# Choin_tran1_0.net
KiCad netlist of a schematic drawn in Altium Designer
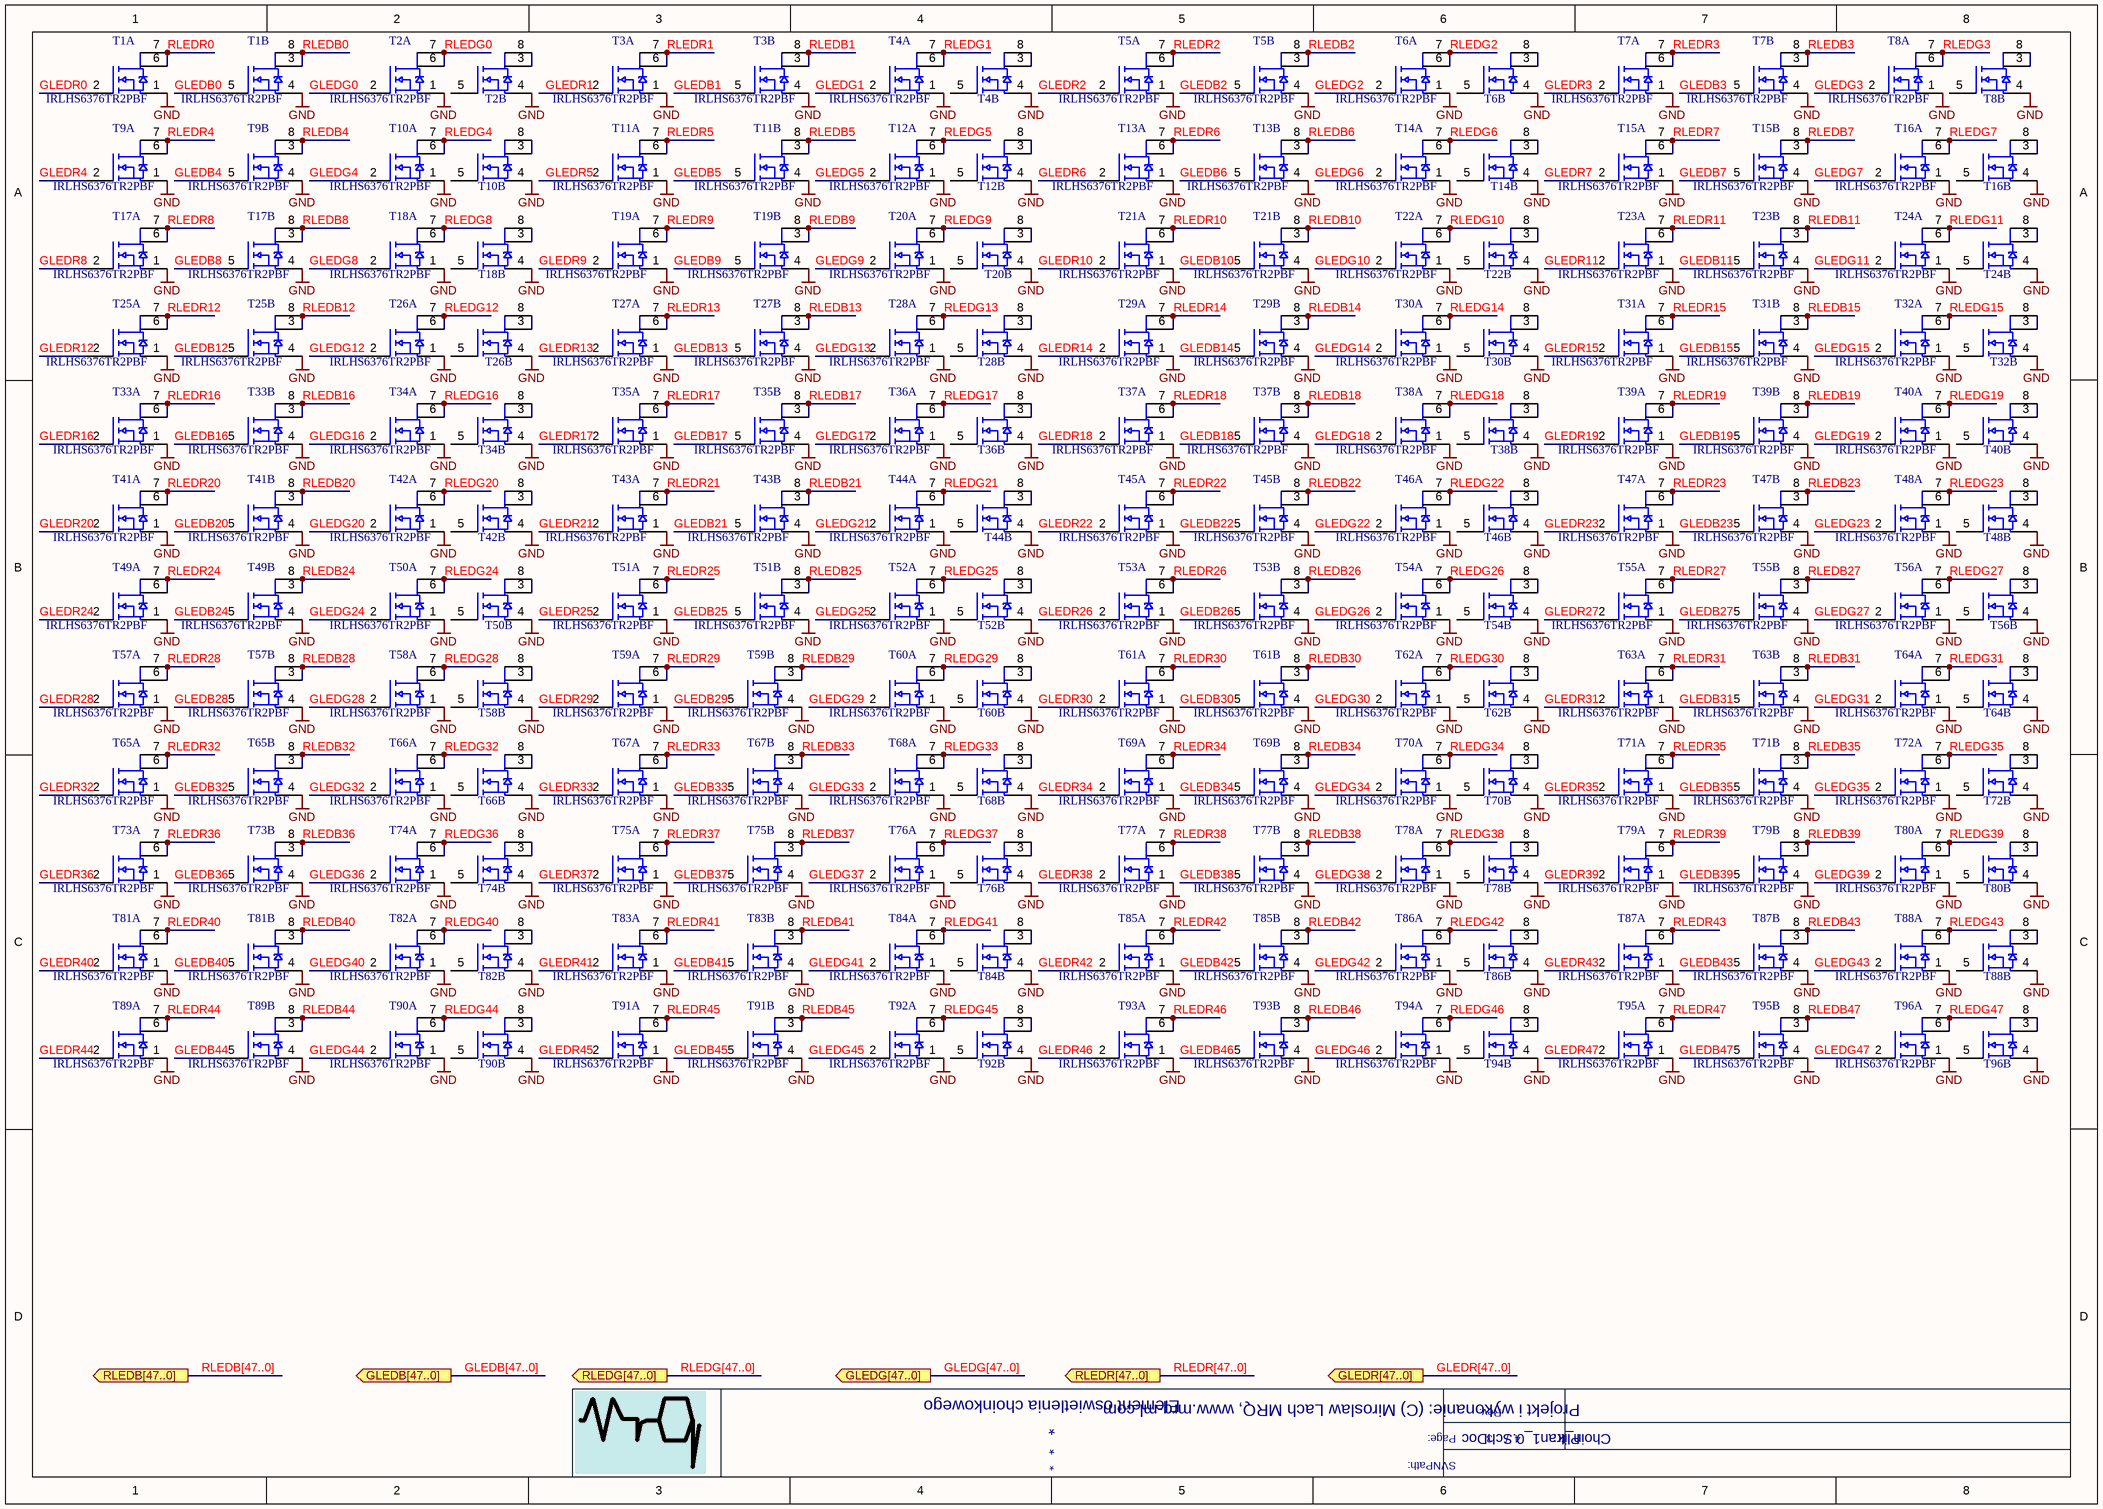
[diagram p0: Choin_tran1_0.SchDoc]

(export (version "E")
  (design (tool "Eeschema 10.0.6"))
  (components
    (comp (ref "T1")
      (value "IRLHS6376TR2PBF")
      (footprint "PQFN2X2DUAL")
      (libsource (lib "Parts") (part "IRLHS6376TR2PBF"))
    )
    (comp (ref "T2")
      (value "IRLHS6376TR2PBF")
      (footprint "PQFN2X2DUAL")
      (libsource (lib "Parts") (part "IRLHS6376TR2PBF"))
    )
    (comp (ref "T3")
      (value "IRLHS6376TR2PBF")
      (footprint "PQFN2X2DUAL")
      (libsource (lib "Parts") (part "IRLHS6376TR2PBF"))
    )
    (comp (ref "T4")
      (value "IRLHS6376TR2PBF")
      (footprint "PQFN2X2DUAL")
      (libsource (lib "Parts") (part "IRLHS6376TR2PBF"))
    )
    (comp (ref "T5")
      (value "IRLHS6376TR2PBF")
      (footprint "PQFN2X2DUAL")
      (libsource (lib "Parts") (part "IRLHS6376TR2PBF"))
    )
    (comp (ref "T6")
      (value "IRLHS6376TR2PBF")
      (footprint "PQFN2X2DUAL")
      (libsource (lib "Parts") (part "IRLHS6376TR2PBF"))
    )
    (comp (ref "T7")
      (value "IRLHS6376TR2PBF")
      (footprint "PQFN2X2DUAL")
      (libsource (lib "Parts") (part "IRLHS6376TR2PBF"))
    )
    (comp (ref "T8")
      (value "IRLHS6376TR2PBF")
      (footprint "PQFN2X2DUAL")
      (libsource (lib "Parts") (part "IRLHS6376TR2PBF"))
    )
    (comp (ref "T9")
      (value "IRLHS6376TR2PBF")
      (footprint "PQFN2X2DUAL")
      (libsource (lib "Parts") (part "IRLHS6376TR2PBF"))
    )
    (comp (ref "T10")
      (value "IRLHS6376TR2PBF")
      (footprint "PQFN2X2DUAL")
      (libsource (lib "Parts") (part "IRLHS6376TR2PBF"))
    )
    (comp (ref "T11")
      (value "IRLHS6376TR2PBF")
      (footprint "PQFN2X2DUAL")
      (libsource (lib "Parts") (part "IRLHS6376TR2PBF"))
    )
    (comp (ref "T12")
      (value "IRLHS6376TR2PBF")
      (footprint "PQFN2X2DUAL")
      (libsource (lib "Parts") (part "IRLHS6376TR2PBF"))
    )
    (comp (ref "T13")
      (value "IRLHS6376TR2PBF")
      (footprint "PQFN2X2DUAL")
      (libsource (lib "Parts") (part "IRLHS6376TR2PBF"))
    )
    (comp (ref "T14")
      (value "IRLHS6376TR2PBF")
      (footprint "PQFN2X2DUAL")
      (libsource (lib "Parts") (part "IRLHS6376TR2PBF"))
    )
    (comp (ref "T15")
      (value "IRLHS6376TR2PBF")
      (footprint "PQFN2X2DUAL")
      (libsource (lib "Parts") (part "IRLHS6376TR2PBF"))
    )
    (comp (ref "T16")
      (value "IRLHS6376TR2PBF")
      (footprint "PQFN2X2DUAL")
      (libsource (lib "Parts") (part "IRLHS6376TR2PBF"))
    )
    (comp (ref "T17")
      (value "IRLHS6376TR2PBF")
      (footprint "PQFN2X2DUAL")
      (libsource (lib "Parts") (part "IRLHS6376TR2PBF"))
    )
    (comp (ref "T18")
      (value "IRLHS6376TR2PBF")
      (footprint "PQFN2X2DUAL")
      (libsource (lib "Parts") (part "IRLHS6376TR2PBF"))
    )
    (comp (ref "T19")
      (value "IRLHS6376TR2PBF")
      (footprint "PQFN2X2DUAL")
      (libsource (lib "Parts") (part "IRLHS6376TR2PBF"))
    )
    (comp (ref "T20")
      (value "IRLHS6376TR2PBF")
      (footprint "PQFN2X2DUAL")
      (libsource (lib "Parts") (part "IRLHS6376TR2PBF"))
    )
    (comp (ref "T21")
      (value "IRLHS6376TR2PBF")
      (footprint "PQFN2X2DUAL")
      (libsource (lib "Parts") (part "IRLHS6376TR2PBF"))
    )
    (comp (ref "T22")
      (value "IRLHS6376TR2PBF")
      (footprint "PQFN2X2DUAL")
      (libsource (lib "Parts") (part "IRLHS6376TR2PBF"))
    )
    (comp (ref "T23")
      (value "IRLHS6376TR2PBF")
      (footprint "PQFN2X2DUAL")
      (libsource (lib "Parts") (part "IRLHS6376TR2PBF"))
    )
    (comp (ref "T24")
      (value "IRLHS6376TR2PBF")
      (footprint "PQFN2X2DUAL")
      (libsource (lib "Parts") (part "IRLHS6376TR2PBF"))
    )
    (comp (ref "T25")
      (value "IRLHS6376TR2PBF")
      (footprint "PQFN2X2DUAL")
      (libsource (lib "Parts") (part "IRLHS6376TR2PBF"))
    )
    (comp (ref "T26")
      (value "IRLHS6376TR2PBF")
      (footprint "PQFN2X2DUAL")
      (libsource (lib "Parts") (part "IRLHS6376TR2PBF"))
    )
    (comp (ref "T27")
      (value "IRLHS6376TR2PBF")
      (footprint "PQFN2X2DUAL")
      (libsource (lib "Parts") (part "IRLHS6376TR2PBF"))
    )
    (comp (ref "T28")
      (value "IRLHS6376TR2PBF")
      (footprint "PQFN2X2DUAL")
      (libsource (lib "Parts") (part "IRLHS6376TR2PBF"))
    )
    (comp (ref "T29")
      (value "IRLHS6376TR2PBF")
      (footprint "PQFN2X2DUAL")
      (libsource (lib "Parts") (part "IRLHS6376TR2PBF"))
    )
    (comp (ref "T30")
      (value "IRLHS6376TR2PBF")
      (footprint "PQFN2X2DUAL")
      (libsource (lib "Parts") (part "IRLHS6376TR2PBF"))
    )
    (comp (ref "T31")
      (value "IRLHS6376TR2PBF")
      (footprint "PQFN2X2DUAL")
      (libsource (lib "Parts") (part "IRLHS6376TR2PBF"))
    )
    (comp (ref "T32")
      (value "IRLHS6376TR2PBF")
      (footprint "PQFN2X2DUAL")
      (libsource (lib "Parts") (part "IRLHS6376TR2PBF"))
    )
    (comp (ref "T33")
      (value "IRLHS6376TR2PBF")
      (footprint "PQFN2X2DUAL")
      (libsource (lib "Parts") (part "IRLHS6376TR2PBF"))
    )
    (comp (ref "T34")
      (value "IRLHS6376TR2PBF")
      (footprint "PQFN2X2DUAL")
      (libsource (lib "Parts") (part "IRLHS6376TR2PBF"))
    )
    (comp (ref "T35")
      (value "IRLHS6376TR2PBF")
      (footprint "PQFN2X2DUAL")
      (libsource (lib "Parts") (part "IRLHS6376TR2PBF"))
    )
    (comp (ref "T36")
      (value "IRLHS6376TR2PBF")
      (footprint "PQFN2X2DUAL")
      (libsource (lib "Parts") (part "IRLHS6376TR2PBF"))
    )
    (comp (ref "T37")
      (value "IRLHS6376TR2PBF")
      (footprint "PQFN2X2DUAL")
      (libsource (lib "Parts") (part "IRLHS6376TR2PBF"))
    )
    (comp (ref "T38")
      (value "IRLHS6376TR2PBF")
      (footprint "PQFN2X2DUAL")
      (libsource (lib "Parts") (part "IRLHS6376TR2PBF"))
    )
    (comp (ref "T39")
      (value "IRLHS6376TR2PBF")
      (footprint "PQFN2X2DUAL")
      (libsource (lib "Parts") (part "IRLHS6376TR2PBF"))
    )
    (comp (ref "T40")
      (value "IRLHS6376TR2PBF")
      (footprint "PQFN2X2DUAL")
      (libsource (lib "Parts") (part "IRLHS6376TR2PBF"))
    )
    (comp (ref "T41")
      (value "IRLHS6376TR2PBF")
      (footprint "PQFN2X2DUAL")
      (libsource (lib "Parts") (part "IRLHS6376TR2PBF"))
    )
    (comp (ref "T42")
      (value "IRLHS6376TR2PBF")
      (footprint "PQFN2X2DUAL")
      (libsource (lib "Parts") (part "IRLHS6376TR2PBF"))
    )
    (comp (ref "T43")
      (value "IRLHS6376TR2PBF")
      (footprint "PQFN2X2DUAL")
      (libsource (lib "Parts") (part "IRLHS6376TR2PBF"))
    )
    (comp (ref "T44")
      (value "IRLHS6376TR2PBF")
      (footprint "PQFN2X2DUAL")
      (libsource (lib "Parts") (part "IRLHS6376TR2PBF"))
    )
    (comp (ref "T45")
      (value "IRLHS6376TR2PBF")
      (footprint "PQFN2X2DUAL")
      (libsource (lib "Parts") (part "IRLHS6376TR2PBF"))
    )
    (comp (ref "T46")
      (value "IRLHS6376TR2PBF")
      (footprint "PQFN2X2DUAL")
      (libsource (lib "Parts") (part "IRLHS6376TR2PBF"))
    )
    (comp (ref "T47")
      (value "IRLHS6376TR2PBF")
      (footprint "PQFN2X2DUAL")
      (libsource (lib "Parts") (part "IRLHS6376TR2PBF"))
    )
    (comp (ref "T48")
      (value "IRLHS6376TR2PBF")
      (footprint "PQFN2X2DUAL")
      (libsource (lib "Parts") (part "IRLHS6376TR2PBF"))
    )
    (comp (ref "T49")
      (value "IRLHS6376TR2PBF")
      (footprint "PQFN2X2DUAL")
      (libsource (lib "Parts") (part "IRLHS6376TR2PBF"))
    )
    (comp (ref "T50")
      (value "IRLHS6376TR2PBF")
      (footprint "PQFN2X2DUAL")
      (libsource (lib "Parts") (part "IRLHS6376TR2PBF"))
    )
    (comp (ref "T51")
      (value "IRLHS6376TR2PBF")
      (footprint "PQFN2X2DUAL")
      (libsource (lib "Parts") (part "IRLHS6376TR2PBF"))
    )
    (comp (ref "T52")
      (value "IRLHS6376TR2PBF")
      (footprint "PQFN2X2DUAL")
      (libsource (lib "Parts") (part "IRLHS6376TR2PBF"))
    )
    (comp (ref "T53")
      (value "IRLHS6376TR2PBF")
      (footprint "PQFN2X2DUAL")
      (libsource (lib "Parts") (part "IRLHS6376TR2PBF"))
    )
    (comp (ref "T54")
      (value "IRLHS6376TR2PBF")
      (footprint "PQFN2X2DUAL")
      (libsource (lib "Parts") (part "IRLHS6376TR2PBF"))
    )
    (comp (ref "T55")
      (value "IRLHS6376TR2PBF")
      (footprint "PQFN2X2DUAL")
      (libsource (lib "Parts") (part "IRLHS6376TR2PBF"))
    )
    (comp (ref "T56")
      (value "IRLHS6376TR2PBF")
      (footprint "PQFN2X2DUAL")
      (libsource (lib "Parts") (part "IRLHS6376TR2PBF"))
    )
    (comp (ref "T57")
      (value "IRLHS6376TR2PBF")
      (footprint "PQFN2X2DUAL")
      (libsource (lib "Parts") (part "IRLHS6376TR2PBF"))
    )
    (comp (ref "T58")
      (value "IRLHS6376TR2PBF")
      (footprint "PQFN2X2DUAL")
      (libsource (lib "Parts") (part "IRLHS6376TR2PBF"))
    )
    (comp (ref "T59")
      (value "IRLHS6376TR2PBF")
      (footprint "PQFN2X2DUAL")
      (libsource (lib "Parts") (part "IRLHS6376TR2PBF"))
    )
    (comp (ref "T60")
      (value "IRLHS6376TR2PBF")
      (footprint "PQFN2X2DUAL")
      (libsource (lib "Parts") (part "IRLHS6376TR2PBF"))
    )
    (comp (ref "T61")
      (value "IRLHS6376TR2PBF")
      (footprint "PQFN2X2DUAL")
      (libsource (lib "Parts") (part "IRLHS6376TR2PBF"))
    )
    (comp (ref "T62")
      (value "IRLHS6376TR2PBF")
      (footprint "PQFN2X2DUAL")
      (libsource (lib "Parts") (part "IRLHS6376TR2PBF"))
    )
    (comp (ref "T63")
      (value "IRLHS6376TR2PBF")
      (footprint "PQFN2X2DUAL")
      (libsource (lib "Parts") (part "IRLHS6376TR2PBF"))
    )
    (comp (ref "T64")
      (value "IRLHS6376TR2PBF")
      (footprint "PQFN2X2DUAL")
      (libsource (lib "Parts") (part "IRLHS6376TR2PBF"))
    )
    (comp (ref "T65")
      (value "IRLHS6376TR2PBF")
      (footprint "PQFN2X2DUAL")
      (libsource (lib "Parts") (part "IRLHS6376TR2PBF"))
    )
    (comp (ref "T66")
      (value "IRLHS6376TR2PBF")
      (footprint "PQFN2X2DUAL")
      (libsource (lib "Parts") (part "IRLHS6376TR2PBF"))
    )
    (comp (ref "T67")
      (value "IRLHS6376TR2PBF")
      (footprint "PQFN2X2DUAL")
      (libsource (lib "Parts") (part "IRLHS6376TR2PBF"))
    )
    (comp (ref "T68")
      (value "IRLHS6376TR2PBF")
      (footprint "PQFN2X2DUAL")
      (libsource (lib "Parts") (part "IRLHS6376TR2PBF"))
    )
    (comp (ref "T69")
      (value "IRLHS6376TR2PBF")
      (footprint "PQFN2X2DUAL")
      (libsource (lib "Parts") (part "IRLHS6376TR2PBF"))
    )
    (comp (ref "T70")
      (value "IRLHS6376TR2PBF")
      (footprint "PQFN2X2DUAL")
      (libsource (lib "Parts") (part "IRLHS6376TR2PBF"))
    )
    (comp (ref "T71")
      (value "IRLHS6376TR2PBF")
      (footprint "PQFN2X2DUAL")
      (libsource (lib "Parts") (part "IRLHS6376TR2PBF"))
    )
    (comp (ref "T72")
      (value "IRLHS6376TR2PBF")
      (footprint "PQFN2X2DUAL")
      (libsource (lib "Parts") (part "IRLHS6376TR2PBF"))
    )
    (comp (ref "T73")
      (value "IRLHS6376TR2PBF")
      (footprint "PQFN2X2DUAL")
      (libsource (lib "Parts") (part "IRLHS6376TR2PBF"))
    )
    (comp (ref "T74")
      (value "IRLHS6376TR2PBF")
      (footprint "PQFN2X2DUAL")
      (libsource (lib "Parts") (part "IRLHS6376TR2PBF"))
    )
    (comp (ref "T75")
      (value "IRLHS6376TR2PBF")
      (footprint "PQFN2X2DUAL")
      (libsource (lib "Parts") (part "IRLHS6376TR2PBF"))
    )
    (comp (ref "T76")
      (value "IRLHS6376TR2PBF")
      (footprint "PQFN2X2DUAL")
      (libsource (lib "Parts") (part "IRLHS6376TR2PBF"))
    )
    (comp (ref "T77")
      (value "IRLHS6376TR2PBF")
      (footprint "PQFN2X2DUAL")
      (libsource (lib "Parts") (part "IRLHS6376TR2PBF"))
    )
    (comp (ref "T78")
      (value "IRLHS6376TR2PBF")
      (footprint "PQFN2X2DUAL")
      (libsource (lib "Parts") (part "IRLHS6376TR2PBF"))
    )
    (comp (ref "T79")
      (value "IRLHS6376TR2PBF")
      (footprint "PQFN2X2DUAL")
      (libsource (lib "Parts") (part "IRLHS6376TR2PBF"))
    )
    (comp (ref "T80")
      (value "IRLHS6376TR2PBF")
      (footprint "PQFN2X2DUAL")
      (libsource (lib "Parts") (part "IRLHS6376TR2PBF"))
    )
    (comp (ref "T81")
      (value "IRLHS6376TR2PBF")
      (footprint "PQFN2X2DUAL")
      (libsource (lib "Parts") (part "IRLHS6376TR2PBF"))
    )
    (comp (ref "T82")
      (value "IRLHS6376TR2PBF")
      (footprint "PQFN2X2DUAL")
      (libsource (lib "Parts") (part "IRLHS6376TR2PBF"))
    )
    (comp (ref "T83")
      (value "IRLHS6376TR2PBF")
      (footprint "PQFN2X2DUAL")
      (libsource (lib "Parts") (part "IRLHS6376TR2PBF"))
    )
    (comp (ref "T84")
      (value "IRLHS6376TR2PBF")
      (footprint "PQFN2X2DUAL")
      (libsource (lib "Parts") (part "IRLHS6376TR2PBF"))
    )
    (comp (ref "T85")
      (value "IRLHS6376TR2PBF")
      (footprint "PQFN2X2DUAL")
      (libsource (lib "Parts") (part "IRLHS6376TR2PBF"))
    )
    (comp (ref "T86")
      (value "IRLHS6376TR2PBF")
      (footprint "PQFN2X2DUAL")
      (libsource (lib "Parts") (part "IRLHS6376TR2PBF"))
    )
    (comp (ref "T87")
      (value "IRLHS6376TR2PBF")
      (footprint "PQFN2X2DUAL")
      (libsource (lib "Parts") (part "IRLHS6376TR2PBF"))
    )
    (comp (ref "T88")
      (value "IRLHS6376TR2PBF")
      (footprint "PQFN2X2DUAL")
      (libsource (lib "Parts") (part "IRLHS6376TR2PBF"))
    )
    (comp (ref "T89")
      (value "IRLHS6376TR2PBF")
      (footprint "PQFN2X2DUAL")
      (libsource (lib "Parts") (part "IRLHS6376TR2PBF"))
    )
    (comp (ref "T90")
      (value "IRLHS6376TR2PBF")
      (footprint "PQFN2X2DUAL")
      (libsource (lib "Parts") (part "IRLHS6376TR2PBF"))
    )
    (comp (ref "T91")
      (value "IRLHS6376TR2PBF")
      (footprint "PQFN2X2DUAL")
      (libsource (lib "Parts") (part "IRLHS6376TR2PBF"))
    )
    (comp (ref "T92")
      (value "IRLHS6376TR2PBF")
      (footprint "PQFN2X2DUAL")
      (libsource (lib "Parts") (part "IRLHS6376TR2PBF"))
    )
    (comp (ref "T93")
      (value "IRLHS6376TR2PBF")
      (footprint "PQFN2X2DUAL")
      (libsource (lib "Parts") (part "IRLHS6376TR2PBF"))
    )
    (comp (ref "T94")
      (value "IRLHS6376TR2PBF")
      (footprint "PQFN2X2DUAL")
      (libsource (lib "Parts") (part "IRLHS6376TR2PBF"))
    )
    (comp (ref "T95")
      (value "IRLHS6376TR2PBF")
      (footprint "PQFN2X2DUAL")
      (libsource (lib "Parts") (part "IRLHS6376TR2PBF"))
    )
    (comp (ref "T96")
      (value "IRLHS6376TR2PBF")
      (footprint "PQFN2X2DUAL")
      (libsource (lib "Parts") (part "IRLHS6376TR2PBF"))
    )
  )
  (nets
    (net (code "1") (name "/GLEDB0") (class "Default")
      (node (ref "T1") (pin "5") (pinfunction "G2_5") (pintype "passive"))
    )
    (net (code "2") (name "/GLEDB1") (class "Default")
      (node (ref "T3") (pin "5") (pinfunction "G2_5") (pintype "passive"))
    )
    (net (code "3") (name "/GLEDB2") (class "Default")
      (node (ref "T5") (pin "5") (pinfunction "G2_5") (pintype "passive"))
    )
    (net (code "4") (name "/GLEDB3") (class "Default")
      (node (ref "T7") (pin "5") (pinfunction "G2_5") (pintype "passive"))
    )
    (net (code "5") (name "/GLEDB4") (class "Default")
      (node (ref "T9") (pin "5") (pinfunction "G2_5") (pintype "passive"))
    )
    (net (code "6") (name "/GLEDB5") (class "Default")
      (node (ref "T11") (pin "5") (pinfunction "G2_5") (pintype "passive"))
    )
    (net (code "7") (name "/GLEDB6") (class "Default")
      (node (ref "T13") (pin "5") (pinfunction "G2_5") (pintype "passive"))
    )
    (net (code "8") (name "/GLEDB7") (class "Default")
      (node (ref "T15") (pin "5") (pinfunction "G2_5") (pintype "passive"))
    )
    (net (code "9") (name "/GLEDB8") (class "Default")
      (node (ref "T17") (pin "5") (pinfunction "G2_5") (pintype "passive"))
    )
    (net (code "10") (name "/GLEDB9") (class "Default")
      (node (ref "T19") (pin "5") (pinfunction "G2_5") (pintype "passive"))
    )
    (net (code "11") (name "/GLEDB10") (class "Default")
      (node (ref "T21") (pin "5") (pinfunction "G2_5") (pintype "passive"))
    )
    (net (code "12") (name "/GLEDB11") (class "Default")
      (node (ref "T23") (pin "5") (pinfunction "G2_5") (pintype "passive"))
    )
    (net (code "13") (name "/GLEDB12") (class "Default")
      (node (ref "T25") (pin "5") (pinfunction "G2_5") (pintype "passive"))
    )
    (net (code "14") (name "/GLEDB13") (class "Default")
      (node (ref "T27") (pin "5") (pinfunction "G2_5") (pintype "passive"))
    )
    (net (code "15") (name "/GLEDB14") (class "Default")
      (node (ref "T29") (pin "5") (pinfunction "G2_5") (pintype "passive"))
    )
    (net (code "16") (name "/GLEDB15") (class "Default")
      (node (ref "T31") (pin "5") (pinfunction "G2_5") (pintype "passive"))
    )
    (net (code "17") (name "/GLEDB16") (class "Default")
      (node (ref "T33") (pin "5") (pinfunction "G2_5") (pintype "passive"))
    )
    (net (code "18") (name "/GLEDB17") (class "Default")
      (node (ref "T35") (pin "5") (pinfunction "G2_5") (pintype "passive"))
    )
    (net (code "19") (name "/GLEDB18") (class "Default")
      (node (ref "T37") (pin "5") (pinfunction "G2_5") (pintype "passive"))
    )
    (net (code "20") (name "/GLEDB19") (class "Default")
      (node (ref "T39") (pin "5") (pinfunction "G2_5") (pintype "passive"))
    )
    (net (code "21") (name "/GLEDB20") (class "Default")
      (node (ref "T41") (pin "5") (pinfunction "G2_5") (pintype "passive"))
    )
    (net (code "22") (name "/GLEDB21") (class "Default")
      (node (ref "T43") (pin "5") (pinfunction "G2_5") (pintype "passive"))
    )
    (net (code "23") (name "/GLEDB22") (class "Default")
      (node (ref "T45") (pin "5") (pinfunction "G2_5") (pintype "passive"))
    )
    (net (code "24") (name "/GLEDB23") (class "Default")
      (node (ref "T47") (pin "5") (pinfunction "G2_5") (pintype "passive"))
    )
    (net (code "25") (name "/GLEDB24") (class "Default")
      (node (ref "T49") (pin "5") (pinfunction "G2_5") (pintype "passive"))
    )
    (net (code "26") (name "/GLEDB25") (class "Default")
      (node (ref "T51") (pin "5") (pinfunction "G2_5") (pintype "passive"))
    )
    (net (code "27") (name "/GLEDB26") (class "Default")
      (node (ref "T53") (pin "5") (pinfunction "G2_5") (pintype "passive"))
    )
    (net (code "28") (name "/GLEDB27") (class "Default")
      (node (ref "T55") (pin "5") (pinfunction "G2_5") (pintype "passive"))
    )
    (net (code "29") (name "/GLEDB28") (class "Default")
      (node (ref "T57") (pin "5") (pinfunction "G2_5") (pintype "passive"))
    )
    (net (code "30") (name "/GLEDB29") (class "Default")
      (node (ref "T59") (pin "5") (pinfunction "G2_5") (pintype "passive"))
    )
    (net (code "31") (name "/GLEDB30") (class "Default")
      (node (ref "T61") (pin "5") (pinfunction "G2_5") (pintype "passive"))
    )
    (net (code "32") (name "/GLEDB31") (class "Default")
      (node (ref "T63") (pin "5") (pinfunction "G2_5") (pintype "passive"))
    )
    (net (code "33") (name "/GLEDB32") (class "Default")
      (node (ref "T65") (pin "5") (pinfunction "G2_5") (pintype "passive"))
    )
    (net (code "34") (name "/GLEDB33") (class "Default")
      (node (ref "T67") (pin "5") (pinfunction "G2_5") (pintype "passive"))
    )
    (net (code "35") (name "/GLEDB34") (class "Default")
      (node (ref "T69") (pin "5") (pinfunction "G2_5") (pintype "passive"))
    )
    (net (code "36") (name "/GLEDB35") (class "Default")
      (node (ref "T71") (pin "5") (pinfunction "G2_5") (pintype "passive"))
    )
    (net (code "37") (name "/GLEDB36") (class "Default")
      (node (ref "T73") (pin "5") (pinfunction "G2_5") (pintype "passive"))
    )
    (net (code "38") (name "/GLEDB37") (class "Default")
      (node (ref "T75") (pin "5") (pinfunction "G2_5") (pintype "passive"))
    )
    (net (code "39") (name "/GLEDB38") (class "Default")
      (node (ref "T77") (pin "5") (pinfunction "G2_5") (pintype "passive"))
    )
    (net (code "40") (name "/GLEDB39") (class "Default")
      (node (ref "T79") (pin "5") (pinfunction "G2_5") (pintype "passive"))
    )
    (net (code "41") (name "/GLEDB40") (class "Default")
      (node (ref "T81") (pin "5") (pinfunction "G2_5") (pintype "passive"))
    )
    (net (code "42") (name "/GLEDB41") (class "Default")
      (node (ref "T83") (pin "5") (pinfunction "G2_5") (pintype "passive"))
    )
    (net (code "43") (name "/GLEDB42") (class "Default")
      (node (ref "T85") (pin "5") (pinfunction "G2_5") (pintype "passive"))
    )
    (net (code "44") (name "/GLEDB43") (class "Default")
      (node (ref "T87") (pin "5") (pinfunction "G2_5") (pintype "passive"))
    )
    (net (code "45") (name "/GLEDB44") (class "Default")
      (node (ref "T89") (pin "5") (pinfunction "G2_5") (pintype "passive"))
    )
    (net (code "46") (name "/GLEDB45") (class "Default")
      (node (ref "T91") (pin "5") (pinfunction "G2_5") (pintype "passive"))
    )
    (net (code "47") (name "/GLEDB46") (class "Default")
      (node (ref "T93") (pin "5") (pinfunction "G2_5") (pintype "passive"))
    )
    (net (code "48") (name "/GLEDB47") (class "Default")
      (node (ref "T95") (pin "5") (pinfunction "G2_5") (pintype "passive"))
    )
    (net (code "50") (name "/GLEDG0") (class "Default")
      (node (ref "T2") (pin "2") (pinfunction "G1_2") (pintype "passive"))
    )
    (net (code "51") (name "/GLEDG1") (class "Default")
      (node (ref "T4") (pin "2") (pinfunction "G1_2") (pintype "passive"))
    )
    (net (code "52") (name "/GLEDG2") (class "Default")
      (node (ref "T6") (pin "2") (pinfunction "G1_2") (pintype "passive"))
    )
    (net (code "53") (name "/GLEDG3") (class "Default")
      (node (ref "T8") (pin "2") (pinfunction "G1_2") (pintype "passive"))
    )
    (net (code "54") (name "/GLEDG4") (class "Default")
      (node (ref "T10") (pin "2") (pinfunction "G1_2") (pintype "passive"))
    )
    (net (code "55") (name "/GLEDG5") (class "Default")
      (node (ref "T12") (pin "2") (pinfunction "G1_2") (pintype "passive"))
    )
    (net (code "56") (name "/GLEDG6") (class "Default")
      (node (ref "T14") (pin "2") (pinfunction "G1_2") (pintype "passive"))
    )
    (net (code "57") (name "/GLEDG7") (class "Default")
      (node (ref "T16") (pin "2") (pinfunction "G1_2") (pintype "passive"))
    )
    (net (code "58") (name "/GLEDG8") (class "Default")
      (node (ref "T18") (pin "2") (pinfunction "G1_2") (pintype "passive"))
    )
    (net (code "59") (name "/GLEDG9") (class "Default")
      (node (ref "T20") (pin "2") (pinfunction "G1_2") (pintype "passive"))
    )
    (net (code "60") (name "/GLEDG10") (class "Default")
      (node (ref "T22") (pin "2") (pinfunction "G1_2") (pintype "passive"))
    )
    (net (code "61") (name "/GLEDG11") (class "Default")
      (node (ref "T24") (pin "2") (pinfunction "G1_2") (pintype "passive"))
    )
    (net (code "62") (name "/GLEDG12") (class "Default")
      (node (ref "T26") (pin "2") (pinfunction "G1_2") (pintype "passive"))
    )
    (net (code "63") (name "/GLEDG13") (class "Default")
      (node (ref "T28") (pin "2") (pinfunction "G1_2") (pintype "passive"))
    )
    (net (code "64") (name "/GLEDG14") (class "Default")
      (node (ref "T30") (pin "2") (pinfunction "G1_2") (pintype "passive"))
    )
    (net (code "65") (name "/GLEDG15") (class "Default")
      (node (ref "T32") (pin "2") (pinfunction "G1_2") (pintype "passive"))
    )
    (net (code "66") (name "/GLEDG16") (class "Default")
      (node (ref "T34") (pin "2") (pinfunction "G1_2") (pintype "passive"))
    )
    (net (code "67") (name "/GLEDG17") (class "Default")
      (node (ref "T36") (pin "2") (pinfunction "G1_2") (pintype "passive"))
    )
    (net (code "68") (name "/GLEDG18") (class "Default")
      (node (ref "T38") (pin "2") (pinfunction "G1_2") (pintype "passive"))
    )
    (net (code "69") (name "/GLEDG19") (class "Default")
      (node (ref "T40") (pin "2") (pinfunction "G1_2") (pintype "passive"))
    )
    (net (code "70") (name "/GLEDG20") (class "Default")
      (node (ref "T42") (pin "2") (pinfunction "G1_2") (pintype "passive"))
    )
    (net (code "71") (name "/GLEDG21") (class "Default")
      (node (ref "T44") (pin "2") (pinfunction "G1_2") (pintype "passive"))
    )
    (net (code "72") (name "/GLEDG22") (class "Default")
      (node (ref "T46") (pin "2") (pinfunction "G1_2") (pintype "passive"))
    )
    (net (code "73") (name "/GLEDG23") (class "Default")
      (node (ref "T48") (pin "2") (pinfunction "G1_2") (pintype "passive"))
    )
    (net (code "74") (name "/GLEDG24") (class "Default")
      (node (ref "T50") (pin "2") (pinfunction "G1_2") (pintype "passive"))
    )
    (net (code "75") (name "/GLEDG25") (class "Default")
      (node (ref "T52") (pin "2") (pinfunction "G1_2") (pintype "passive"))
    )
    (net (code "76") (name "/GLEDG26") (class "Default")
      (node (ref "T54") (pin "2") (pinfunction "G1_2") (pintype "passive"))
    )
    (net (code "77") (name "/GLEDG27") (class "Default")
      (node (ref "T56") (pin "2") (pinfunction "G1_2") (pintype "passive"))
    )
    (net (code "78") (name "/GLEDG28") (class "Default")
      (node (ref "T58") (pin "2") (pinfunction "G1_2") (pintype "passive"))
    )
    (net (code "79") (name "/GLEDG29") (class "Default")
      (node (ref "T60") (pin "2") (pinfunction "G1_2") (pintype "passive"))
    )
    (net (code "80") (name "/GLEDG30") (class "Default")
      (node (ref "T62") (pin "2") (pinfunction "G1_2") (pintype "passive"))
    )
    (net (code "81") (name "/GLEDG31") (class "Default")
      (node (ref "T64") (pin "2") (pinfunction "G1_2") (pintype "passive"))
    )
    (net (code "82") (name "/GLEDG32") (class "Default")
      (node (ref "T66") (pin "2") (pinfunction "G1_2") (pintype "passive"))
    )
    (net (code "83") (name "/GLEDG33") (class "Default")
      (node (ref "T68") (pin "2") (pinfunction "G1_2") (pintype "passive"))
    )
    (net (code "84") (name "/GLEDG34") (class "Default")
      (node (ref "T70") (pin "2") (pinfunction "G1_2") (pintype "passive"))
    )
    (net (code "85") (name "/GLEDG35") (class "Default")
      (node (ref "T72") (pin "2") (pinfunction "G1_2") (pintype "passive"))
    )
    (net (code "86") (name "/GLEDG36") (class "Default")
      (node (ref "T74") (pin "2") (pinfunction "G1_2") (pintype "passive"))
    )
    (net (code "87") (name "/GLEDG37") (class "Default")
      (node (ref "T76") (pin "2") (pinfunction "G1_2") (pintype "passive"))
    )
    (net (code "88") (name "/GLEDG38") (class "Default")
      (node (ref "T78") (pin "2") (pinfunction "G1_2") (pintype "passive"))
    )
    (net (code "89") (name "/GLEDG39") (class "Default")
      (node (ref "T80") (pin "2") (pinfunction "G1_2") (pintype "passive"))
    )
    (net (code "90") (name "/GLEDG40") (class "Default")
      (node (ref "T82") (pin "2") (pinfunction "G1_2") (pintype "passive"))
    )
    (net (code "91") (name "/GLEDG41") (class "Default")
      (node (ref "T84") (pin "2") (pinfunction "G1_2") (pintype "passive"))
    )
    (net (code "92") (name "/GLEDG42") (class "Default")
      (node (ref "T86") (pin "2") (pinfunction "G1_2") (pintype "passive"))
    )
    (net (code "93") (name "/GLEDG43") (class "Default")
      (node (ref "T88") (pin "2") (pinfunction "G1_2") (pintype "passive"))
    )
    (net (code "94") (name "/GLEDG44") (class "Default")
      (node (ref "T90") (pin "2") (pinfunction "G1_2") (pintype "passive"))
    )
    (net (code "95") (name "/GLEDG45") (class "Default")
      (node (ref "T92") (pin "2") (pinfunction "G1_2") (pintype "passive"))
    )
    (net (code "96") (name "/GLEDG46") (class "Default")
      (node (ref "T94") (pin "2") (pinfunction "G1_2") (pintype "passive"))
    )
    (net (code "97") (name "/GLEDG47") (class "Default")
      (node (ref "T96") (pin "2") (pinfunction "G1_2") (pintype "passive"))
    )
    (net (code "99") (name "/GLEDR0") (class "Default")
      (node (ref "T1") (pin "2") (pinfunction "G1_2") (pintype "passive"))
    )
    (net (code "100") (name "/GLEDR1") (class "Default")
      (node (ref "T3") (pin "2") (pinfunction "G1_2") (pintype "passive"))
    )
    (net (code "101") (name "/GLEDR2") (class "Default")
      (node (ref "T5") (pin "2") (pinfunction "G1_2") (pintype "passive"))
    )
    (net (code "102") (name "/GLEDR3") (class "Default")
      (node (ref "T7") (pin "2") (pinfunction "G1_2") (pintype "passive"))
    )
    (net (code "103") (name "/GLEDR4") (class "Default")
      (node (ref "T9") (pin "2") (pinfunction "G1_2") (pintype "passive"))
    )
    (net (code "104") (name "/GLEDR5") (class "Default")
      (node (ref "T11") (pin "2") (pinfunction "G1_2") (pintype "passive"))
    )
    (net (code "105") (name "/GLEDR6") (class "Default")
      (node (ref "T13") (pin "2") (pinfunction "G1_2") (pintype "passive"))
    )
    (net (code "106") (name "/GLEDR7") (class "Default")
      (node (ref "T15") (pin "2") (pinfunction "G1_2") (pintype "passive"))
    )
    (net (code "107") (name "/GLEDR8") (class "Default")
      (node (ref "T17") (pin "2") (pinfunction "G1_2") (pintype "passive"))
    )
    (net (code "108") (name "/GLEDR9") (class "Default")
      (node (ref "T19") (pin "2") (pinfunction "G1_2") (pintype "passive"))
    )
    (net (code "109") (name "/GLEDR10") (class "Default")
      (node (ref "T21") (pin "2") (pinfunction "G1_2") (pintype "passive"))
    )
    (net (code "110") (name "/GLEDR11") (class "Default")
      (node (ref "T23") (pin "2") (pinfunction "G1_2") (pintype "passive"))
    )
    (net (code "111") (name "/GLEDR12") (class "Default")
      (node (ref "T25") (pin "2") (pinfunction "G1_2") (pintype "passive"))
    )
    (net (code "112") (name "/GLEDR13") (class "Default")
      (node (ref "T27") (pin "2") (pinfunction "G1_2") (pintype "passive"))
    )
    (net (code "113") (name "/GLEDR14") (class "Default")
      (node (ref "T29") (pin "2") (pinfunction "G1_2") (pintype "passive"))
    )
    (net (code "114") (name "/GLEDR15") (class "Default")
      (node (ref "T31") (pin "2") (pinfunction "G1_2") (pintype "passive"))
    )
    (net (code "115") (name "/GLEDR16") (class "Default")
      (node (ref "T33") (pin "2") (pinfunction "G1_2") (pintype "passive"))
    )
    (net (code "116") (name "/GLEDR17") (class "Default")
      (node (ref "T35") (pin "2") (pinfunction "G1_2") (pintype "passive"))
    )
    (net (code "117") (name "/GLEDR18") (class "Default")
      (node (ref "T37") (pin "2") (pinfunction "G1_2") (pintype "passive"))
    )
    (net (code "118") (name "/GLEDR19") (class "Default")
      (node (ref "T39") (pin "2") (pinfunction "G1_2") (pintype "passive"))
    )
    (net (code "119") (name "/GLEDR20") (class "Default")
      (node (ref "T41") (pin "2") (pinfunction "G1_2") (pintype "passive"))
    )
    (net (code "120") (name "/GLEDR21") (class "Default")
      (node (ref "T43") (pin "2") (pinfunction "G1_2") (pintype "passive"))
    )
    (net (code "121") (name "/GLEDR22") (class "Default")
      (node (ref "T45") (pin "2") (pinfunction "G1_2") (pintype "passive"))
    )
    (net (code "122") (name "/GLEDR23") (class "Default")
      (node (ref "T47") (pin "2") (pinfunction "G1_2") (pintype "passive"))
    )
    (net (code "123") (name "/GLEDR24") (class "Default")
      (node (ref "T49") (pin "2") (pinfunction "G1_2") (pintype "passive"))
    )
    (net (code "124") (name "/GLEDR25") (class "Default")
      (node (ref "T51") (pin "2") (pinfunction "G1_2") (pintype "passive"))
    )
    (net (code "125") (name "/GLEDR26") (class "Default")
      (node (ref "T53") (pin "2") (pinfunction "G1_2") (pintype "passive"))
    )
    (net (code "126") (name "/GLEDR27") (class "Default")
      (node (ref "T55") (pin "2") (pinfunction "G1_2") (pintype "passive"))
    )
    (net (code "127") (name "/GLEDR28") (class "Default")
      (node (ref "T57") (pin "2") (pinfunction "G1_2") (pintype "passive"))
    )
    (net (code "128") (name "/GLEDR29") (class "Default")
      (node (ref "T59") (pin "2") (pinfunction "G1_2") (pintype "passive"))
    )
    (net (code "129") (name "/GLEDR30") (class "Default")
      (node (ref "T61") (pin "2") (pinfunction "G1_2") (pintype "passive"))
    )
    (net (code "130") (name "/GLEDR31") (class "Default")
      (node (ref "T63") (pin "2") (pinfunction "G1_2") (pintype "passive"))
    )
    (net (code "131") (name "/GLEDR32") (class "Default")
      (node (ref "T65") (pin "2") (pinfunction "G1_2") (pintype "passive"))
    )
    (net (code "132") (name "/GLEDR33") (class "Default")
      (node (ref "T67") (pin "2") (pinfunction "G1_2") (pintype "passive"))
    )
    (net (code "133") (name "/GLEDR34") (class "Default")
      (node (ref "T69") (pin "2") (pinfunction "G1_2") (pintype "passive"))
    )
    (net (code "134") (name "/GLEDR35") (class "Default")
      (node (ref "T71") (pin "2") (pinfunction "G1_2") (pintype "passive"))
    )
    (net (code "135") (name "/GLEDR36") (class "Default")
      (node (ref "T73") (pin "2") (pinfunction "G1_2") (pintype "passive"))
    )
    (net (code "136") (name "/GLEDR37") (class "Default")
      (node (ref "T75") (pin "2") (pinfunction "G1_2") (pintype "passive"))
    )
    (net (code "137") (name "/GLEDR38") (class "Default")
      (node (ref "T77") (pin "2") (pinfunction "G1_2") (pintype "passive"))
    )
    (net (code "138") (name "/GLEDR39") (class "Default")
      (node (ref "T79") (pin "2") (pinfunction "G1_2") (pintype "passive"))
    )
    (net (code "139") (name "/GLEDR40") (class "Default")
      (node (ref "T81") (pin "2") (pinfunction "G1_2") (pintype "passive"))
    )
    (net (code "140") (name "/GLEDR41") (class "Default")
      (node (ref "T83") (pin "2") (pinfunction "G1_2") (pintype "passive"))
    )
    (net (code "141") (name "/GLEDR42") (class "Default")
      (node (ref "T85") (pin "2") (pinfunction "G1_2") (pintype "passive"))
    )
    (net (code "142") (name "/GLEDR43") (class "Default")
      (node (ref "T87") (pin "2") (pinfunction "G1_2") (pintype "passive"))
    )
    (net (code "143") (name "/GLEDR44") (class "Default")
      (node (ref "T89") (pin "2") (pinfunction "G1_2") (pintype "passive"))
    )
    (net (code "144") (name "/GLEDR45") (class "Default")
      (node (ref "T91") (pin "2") (pinfunction "G1_2") (pintype "passive"))
    )
    (net (code "145") (name "/GLEDR46") (class "Default")
      (node (ref "T93") (pin "2") (pinfunction "G1_2") (pintype "passive"))
    )
    (net (code "146") (name "/GLEDR47") (class "Default")
      (node (ref "T95") (pin "2") (pinfunction "G1_2") (pintype "passive"))
    )
    (net (code "148") (name "/RLEDB0") (class "Default")
      (node (ref "T1") (pin "3") (pinfunction "D2_3") (pintype "passive"))
      (node (ref "T1") (pin "8") (pinfunction "D2_8") (pintype "passive"))
    )
    (net (code "149") (name "/RLEDB1") (class "Default")
      (node (ref "T3") (pin "3") (pinfunction "D2_3") (pintype "passive"))
      (node (ref "T3") (pin "8") (pinfunction "D2_8") (pintype "passive"))
    )
    (net (code "150") (name "/RLEDB2") (class "Default")
      (node (ref "T5") (pin "3") (pinfunction "D2_3") (pintype "passive"))
      (node (ref "T5") (pin "8") (pinfunction "D2_8") (pintype "passive"))
    )
    (net (code "151") (name "/RLEDB3") (class "Default")
      (node (ref "T7") (pin "3") (pinfunction "D2_3") (pintype "passive"))
      (node (ref "T7") (pin "8") (pinfunction "D2_8") (pintype "passive"))
    )
    (net (code "152") (name "/RLEDB4") (class "Default")
      (node (ref "T9") (pin "3") (pinfunction "D2_3") (pintype "passive"))
      (node (ref "T9") (pin "8") (pinfunction "D2_8") (pintype "passive"))
    )
    (net (code "153") (name "/RLEDB5") (class "Default")
      (node (ref "T11") (pin "3") (pinfunction "D2_3") (pintype "passive"))
      (node (ref "T11") (pin "8") (pinfunction "D2_8") (pintype "passive"))
    )
    (net (code "154") (name "/RLEDB6") (class "Default")
      (node (ref "T13") (pin "3") (pinfunction "D2_3") (pintype "passive"))
      (node (ref "T13") (pin "8") (pinfunction "D2_8") (pintype "passive"))
    )
    (net (code "155") (name "/RLEDB7") (class "Default")
      (node (ref "T15") (pin "3") (pinfunction "D2_3") (pintype "passive"))
      (node (ref "T15") (pin "8") (pinfunction "D2_8") (pintype "passive"))
    )
    (net (code "156") (name "/RLEDB8") (class "Default")
      (node (ref "T17") (pin "3") (pinfunction "D2_3") (pintype "passive"))
      (node (ref "T17") (pin "8") (pinfunction "D2_8") (pintype "passive"))
    )
    (net (code "157") (name "/RLEDB9") (class "Default")
      (node (ref "T19") (pin "3") (pinfunction "D2_3") (pintype "passive"))
      (node (ref "T19") (pin "8") (pinfunction "D2_8") (pintype "passive"))
    )
    (net (code "158") (name "/RLEDB10") (class "Default")
      (node (ref "T21") (pin "3") (pinfunction "D2_3") (pintype "passive"))
      (node (ref "T21") (pin "8") (pinfunction "D2_8") (pintype "passive"))
    )
    (net (code "159") (name "/RLEDB11") (class "Default")
      (node (ref "T23") (pin "3") (pinfunction "D2_3") (pintype "passive"))
      (node (ref "T23") (pin "8") (pinfunction "D2_8") (pintype "passive"))
    )
    (net (code "160") (name "/RLEDB12") (class "Default")
      (node (ref "T25") (pin "3") (pinfunction "D2_3") (pintype "passive"))
      (node (ref "T25") (pin "8") (pinfunction "D2_8") (pintype "passive"))
    )
    (net (code "161") (name "/RLEDB13") (class "Default")
      (node (ref "T27") (pin "3") (pinfunction "D2_3") (pintype "passive"))
      (node (ref "T27") (pin "8") (pinfunction "D2_8") (pintype "passive"))
    )
    (net (code "162") (name "/RLEDB14") (class "Default")
      (node (ref "T29") (pin "3") (pinfunction "D2_3") (pintype "passive"))
      (node (ref "T29") (pin "8") (pinfunction "D2_8") (pintype "passive"))
    )
    (net (code "163") (name "/RLEDB15") (class "Default")
      (node (ref "T31") (pin "3") (pinfunction "D2_3") (pintype "passive"))
      (node (ref "T31") (pin "8") (pinfunction "D2_8") (pintype "passive"))
    )
    (net (code "164") (name "/RLEDB16") (class "Default")
      (node (ref "T33") (pin "3") (pinfunction "D2_3") (pintype "passive"))
      (node (ref "T33") (pin "8") (pinfunction "D2_8") (pintype "passive"))
    )
    (net (code "165") (name "/RLEDB17") (class "Default")
      (node (ref "T35") (pin "3") (pinfunction "D2_3") (pintype "passive"))
      (node (ref "T35") (pin "8") (pinfunction "D2_8") (pintype "passive"))
    )
    (net (code "166") (name "/RLEDB18") (class "Default")
      (node (ref "T37") (pin "3") (pinfunction "D2_3") (pintype "passive"))
      (node (ref "T37") (pin "8") (pinfunction "D2_8") (pintype "passive"))
    )
    (net (code "167") (name "/RLEDB19") (class "Default")
      (node (ref "T39") (pin "3") (pinfunction "D2_3") (pintype "passive"))
      (node (ref "T39") (pin "8") (pinfunction "D2_8") (pintype "passive"))
    )
    (net (code "168") (name "/RLEDB20") (class "Default")
      (node (ref "T41") (pin "3") (pinfunction "D2_3") (pintype "passive"))
      (node (ref "T41") (pin "8") (pinfunction "D2_8") (pintype "passive"))
    )
    (net (code "169") (name "/RLEDB21") (class "Default")
      (node (ref "T43") (pin "3") (pinfunction "D2_3") (pintype "passive"))
      (node (ref "T43") (pin "8") (pinfunction "D2_8") (pintype "passive"))
    )
    (net (code "170") (name "/RLEDB22") (class "Default")
      (node (ref "T45") (pin "3") (pinfunction "D2_3") (pintype "passive"))
      (node (ref "T45") (pin "8") (pinfunction "D2_8") (pintype "passive"))
    )
    (net (code "171") (name "/RLEDB23") (class "Default")
      (node (ref "T47") (pin "3") (pinfunction "D2_3") (pintype "passive"))
      (node (ref "T47") (pin "8") (pinfunction "D2_8") (pintype "passive"))
    )
    (net (code "172") (name "/RLEDB24") (class "Default")
      (node (ref "T49") (pin "3") (pinfunction "D2_3") (pintype "passive"))
      (node (ref "T49") (pin "8") (pinfunction "D2_8") (pintype "passive"))
    )
    (net (code "173") (name "/RLEDB25") (class "Default")
      (node (ref "T51") (pin "3") (pinfunction "D2_3") (pintype "passive"))
      (node (ref "T51") (pin "8") (pinfunction "D2_8") (pintype "passive"))
    )
    (net (code "174") (name "/RLEDB26") (class "Default")
      (node (ref "T53") (pin "3") (pinfunction "D2_3") (pintype "passive"))
      (node (ref "T53") (pin "8") (pinfunction "D2_8") (pintype "passive"))
    )
    (net (code "175") (name "/RLEDB27") (class "Default")
      (node (ref "T55") (pin "3") (pinfunction "D2_3") (pintype "passive"))
      (node (ref "T55") (pin "8") (pinfunction "D2_8") (pintype "passive"))
    )
    (net (code "176") (name "/RLEDB28") (class "Default")
      (node (ref "T57") (pin "3") (pinfunction "D2_3") (pintype "passive"))
      (node (ref "T57") (pin "8") (pinfunction "D2_8") (pintype "passive"))
    )
    (net (code "177") (name "/RLEDB29") (class "Default")
      (node (ref "T59") (pin "3") (pinfunction "D2_3") (pintype "passive"))
      (node (ref "T59") (pin "8") (pinfunction "D2_8") (pintype "passive"))
    )
    (net (code "178") (name "/RLEDB30") (class "Default")
      (node (ref "T61") (pin "3") (pinfunction "D2_3") (pintype "passive"))
      (node (ref "T61") (pin "8") (pinfunction "D2_8") (pintype "passive"))
    )
    (net (code "179") (name "/RLEDB31") (class "Default")
      (node (ref "T63") (pin "3") (pinfunction "D2_3") (pintype "passive"))
      (node (ref "T63") (pin "8") (pinfunction "D2_8") (pintype "passive"))
    )
    (net (code "180") (name "/RLEDB32") (class "Default")
      (node (ref "T65") (pin "3") (pinfunction "D2_3") (pintype "passive"))
      (node (ref "T65") (pin "8") (pinfunction "D2_8") (pintype "passive"))
    )
    (net (code "181") (name "/RLEDB33") (class "Default")
      (node (ref "T67") (pin "3") (pinfunction "D2_3") (pintype "passive"))
      (node (ref "T67") (pin "8") (pinfunction "D2_8") (pintype "passive"))
    )
    (net (code "182") (name "/RLEDB34") (class "Default")
      (node (ref "T69") (pin "3") (pinfunction "D2_3") (pintype "passive"))
      (node (ref "T69") (pin "8") (pinfunction "D2_8") (pintype "passive"))
    )
    (net (code "183") (name "/RLEDB35") (class "Default")
      (node (ref "T71") (pin "3") (pinfunction "D2_3") (pintype "passive"))
      (node (ref "T71") (pin "8") (pinfunction "D2_8") (pintype "passive"))
    )
    (net (code "184") (name "/RLEDB36") (class "Default")
      (node (ref "T73") (pin "3") (pinfunction "D2_3") (pintype "passive"))
      (node (ref "T73") (pin "8") (pinfunction "D2_8") (pintype "passive"))
    )
    (net (code "185") (name "/RLEDB37") (class "Default")
      (node (ref "T75") (pin "3") (pinfunction "D2_3") (pintype "passive"))
      (node (ref "T75") (pin "8") (pinfunction "D2_8") (pintype "passive"))
    )
    (net (code "186") (name "/RLEDB38") (class "Default")
      (node (ref "T77") (pin "3") (pinfunction "D2_3") (pintype "passive"))
      (node (ref "T77") (pin "8") (pinfunction "D2_8") (pintype "passive"))
    )
    (net (code "187") (name "/RLEDB39") (class "Default")
      (node (ref "T79") (pin "3") (pinfunction "D2_3") (pintype "passive"))
      (node (ref "T79") (pin "8") (pinfunction "D2_8") (pintype "passive"))
    )
    (net (code "188") (name "/RLEDB40") (class "Default")
      (node (ref "T81") (pin "3") (pinfunction "D2_3") (pintype "passive"))
      (node (ref "T81") (pin "8") (pinfunction "D2_8") (pintype "passive"))
    )
    (net (code "189") (name "/RLEDB41") (class "Default")
      (node (ref "T83") (pin "3") (pinfunction "D2_3") (pintype "passive"))
      (node (ref "T83") (pin "8") (pinfunction "D2_8") (pintype "passive"))
    )
    (net (code "190") (name "/RLEDB42") (class "Default")
      (node (ref "T85") (pin "3") (pinfunction "D2_3") (pintype "passive"))
      (node (ref "T85") (pin "8") (pinfunction "D2_8") (pintype "passive"))
    )
    (net (code "191") (name "/RLEDB43") (class "Default")
      (node (ref "T87") (pin "3") (pinfunction "D2_3") (pintype "passive"))
      (node (ref "T87") (pin "8") (pinfunction "D2_8") (pintype "passive"))
    )
    (net (code "192") (name "/RLEDB44") (class "Default")
      (node (ref "T89") (pin "3") (pinfunction "D2_3") (pintype "passive"))
      (node (ref "T89") (pin "8") (pinfunction "D2_8") (pintype "passive"))
    )
    (net (code "193") (name "/RLEDB45") (class "Default")
      (node (ref "T91") (pin "3") (pinfunction "D2_3") (pintype "passive"))
      (node (ref "T91") (pin "8") (pinfunction "D2_8") (pintype "passive"))
    )
    (net (code "194") (name "/RLEDB46") (class "Default")
      (node (ref "T93") (pin "3") (pinfunction "D2_3") (pintype "passive"))
      (node (ref "T93") (pin "8") (pinfunction "D2_8") (pintype "passive"))
    )
    (net (code "195") (name "/RLEDB47") (class "Default")
      (node (ref "T95") (pin "3") (pinfunction "D2_3") (pintype "passive"))
      (node (ref "T95") (pin "8") (pinfunction "D2_8") (pintype "passive"))
    )
    (net (code "197") (name "/RLEDG0") (class "Default")
      (node (ref "T2") (pin "6") (pinfunction "D1_6") (pintype "passive"))
      (node (ref "T2") (pin "7") (pinfunction "D1_7") (pintype "passive"))
    )
    (net (code "198") (name "/RLEDG1") (class "Default")
      (node (ref "T4") (pin "6") (pinfunction "D1_6") (pintype "passive"))
      (node (ref "T4") (pin "7") (pinfunction "D1_7") (pintype "passive"))
    )
    (net (code "199") (name "/RLEDG2") (class "Default")
      (node (ref "T6") (pin "6") (pinfunction "D1_6") (pintype "passive"))
      (node (ref "T6") (pin "7") (pinfunction "D1_7") (pintype "passive"))
    )
    (net (code "200") (name "/RLEDG3") (class "Default")
      (node (ref "T8") (pin "6") (pinfunction "D1_6") (pintype "passive"))
      (node (ref "T8") (pin "7") (pinfunction "D1_7") (pintype "passive"))
    )
    (net (code "201") (name "/RLEDG4") (class "Default")
      (node (ref "T10") (pin "6") (pinfunction "D1_6") (pintype "passive"))
      (node (ref "T10") (pin "7") (pinfunction "D1_7") (pintype "passive"))
    )
    (net (code "202") (name "/RLEDG5") (class "Default")
      (node (ref "T12") (pin "6") (pinfunction "D1_6") (pintype "passive"))
      (node (ref "T12") (pin "7") (pinfunction "D1_7") (pintype "passive"))
    )
    (net (code "203") (name "/RLEDG6") (class "Default")
      (node (ref "T14") (pin "6") (pinfunction "D1_6") (pintype "passive"))
      (node (ref "T14") (pin "7") (pinfunction "D1_7") (pintype "passive"))
    )
    (net (code "204") (name "/RLEDG7") (class "Default")
      (node (ref "T16") (pin "6") (pinfunction "D1_6") (pintype "passive"))
      (node (ref "T16") (pin "7") (pinfunction "D1_7") (pintype "passive"))
    )
    (net (code "205") (name "/RLEDG8") (class "Default")
      (node (ref "T18") (pin "6") (pinfunction "D1_6") (pintype "passive"))
      (node (ref "T18") (pin "7") (pinfunction "D1_7") (pintype "passive"))
    )
    (net (code "206") (name "/RLEDG9") (class "Default")
      (node (ref "T20") (pin "6") (pinfunction "D1_6") (pintype "passive"))
      (node (ref "T20") (pin "7") (pinfunction "D1_7") (pintype "passive"))
    )
    (net (code "207") (name "/RLEDG10") (class "Default")
      (node (ref "T22") (pin "6") (pinfunction "D1_6") (pintype "passive"))
      (node (ref "T22") (pin "7") (pinfunction "D1_7") (pintype "passive"))
    )
    (net (code "208") (name "/RLEDG11") (class "Default")
      (node (ref "T24") (pin "6") (pinfunction "D1_6") (pintype "passive"))
      (node (ref "T24") (pin "7") (pinfunction "D1_7") (pintype "passive"))
    )
    (net (code "209") (name "/RLEDG12") (class "Default")
      (node (ref "T26") (pin "6") (pinfunction "D1_6") (pintype "passive"))
      (node (ref "T26") (pin "7") (pinfunction "D1_7") (pintype "passive"))
    )
    (net (code "210") (name "/RLEDG13") (class "Default")
      (node (ref "T28") (pin "6") (pinfunction "D1_6") (pintype "passive"))
      (node (ref "T28") (pin "7") (pinfunction "D1_7") (pintype "passive"))
    )
    (net (code "211") (name "/RLEDG14") (class "Default")
      (node (ref "T30") (pin "6") (pinfunction "D1_6") (pintype "passive"))
      (node (ref "T30") (pin "7") (pinfunction "D1_7") (pintype "passive"))
    )
    (net (code "212") (name "/RLEDG15") (class "Default")
      (node (ref "T32") (pin "6") (pinfunction "D1_6") (pintype "passive"))
      (node (ref "T32") (pin "7") (pinfunction "D1_7") (pintype "passive"))
    )
    (net (code "213") (name "/RLEDG16") (class "Default")
      (node (ref "T34") (pin "6") (pinfunction "D1_6") (pintype "passive"))
      (node (ref "T34") (pin "7") (pinfunction "D1_7") (pintype "passive"))
    )
    (net (code "214") (name "/RLEDG17") (class "Default")
      (node (ref "T36") (pin "6") (pinfunction "D1_6") (pintype "passive"))
      (node (ref "T36") (pin "7") (pinfunction "D1_7") (pintype "passive"))
    )
    (net (code "215") (name "/RLEDG18") (class "Default")
      (node (ref "T38") (pin "6") (pinfunction "D1_6") (pintype "passive"))
      (node (ref "T38") (pin "7") (pinfunction "D1_7") (pintype "passive"))
    )
    (net (code "216") (name "/RLEDG19") (class "Default")
      (node (ref "T40") (pin "6") (pinfunction "D1_6") (pintype "passive"))
      (node (ref "T40") (pin "7") (pinfunction "D1_7") (pintype "passive"))
    )
    (net (code "217") (name "/RLEDG20") (class "Default")
      (node (ref "T42") (pin "6") (pinfunction "D1_6") (pintype "passive"))
      (node (ref "T42") (pin "7") (pinfunction "D1_7") (pintype "passive"))
    )
    (net (code "218") (name "/RLEDG21") (class "Default")
      (node (ref "T44") (pin "6") (pinfunction "D1_6") (pintype "passive"))
      (node (ref "T44") (pin "7") (pinfunction "D1_7") (pintype "passive"))
    )
    (net (code "219") (name "/RLEDG22") (class "Default")
      (node (ref "T46") (pin "6") (pinfunction "D1_6") (pintype "passive"))
      (node (ref "T46") (pin "7") (pinfunction "D1_7") (pintype "passive"))
    )
    (net (code "220") (name "/RLEDG23") (class "Default")
      (node (ref "T48") (pin "6") (pinfunction "D1_6") (pintype "passive"))
      (node (ref "T48") (pin "7") (pinfunction "D1_7") (pintype "passive"))
    )
    (net (code "221") (name "/RLEDG24") (class "Default")
      (node (ref "T50") (pin "6") (pinfunction "D1_6") (pintype "passive"))
      (node (ref "T50") (pin "7") (pinfunction "D1_7") (pintype "passive"))
    )
    (net (code "222") (name "/RLEDG25") (class "Default")
      (node (ref "T52") (pin "6") (pinfunction "D1_6") (pintype "passive"))
      (node (ref "T52") (pin "7") (pinfunction "D1_7") (pintype "passive"))
    )
    (net (code "223") (name "/RLEDG26") (class "Default")
      (node (ref "T54") (pin "6") (pinfunction "D1_6") (pintype "passive"))
      (node (ref "T54") (pin "7") (pinfunction "D1_7") (pintype "passive"))
    )
    (net (code "224") (name "/RLEDG27") (class "Default")
      (node (ref "T56") (pin "6") (pinfunction "D1_6") (pintype "passive"))
      (node (ref "T56") (pin "7") (pinfunction "D1_7") (pintype "passive"))
    )
    (net (code "225") (name "/RLEDG28") (class "Default")
      (node (ref "T58") (pin "6") (pinfunction "D1_6") (pintype "passive"))
      (node (ref "T58") (pin "7") (pinfunction "D1_7") (pintype "passive"))
    )
    (net (code "226") (name "/RLEDG29") (class "Default")
      (node (ref "T60") (pin "6") (pinfunction "D1_6") (pintype "passive"))
      (node (ref "T60") (pin "7") (pinfunction "D1_7") (pintype "passive"))
    )
    (net (code "227") (name "/RLEDG30") (class "Default")
      (node (ref "T62") (pin "6") (pinfunction "D1_6") (pintype "passive"))
      (node (ref "T62") (pin "7") (pinfunction "D1_7") (pintype "passive"))
    )
    (net (code "228") (name "/RLEDG31") (class "Default")
      (node (ref "T64") (pin "6") (pinfunction "D1_6") (pintype "passive"))
      (node (ref "T64") (pin "7") (pinfunction "D1_7") (pintype "passive"))
    )
    (net (code "229") (name "/RLEDG32") (class "Default")
      (node (ref "T66") (pin "6") (pinfunction "D1_6") (pintype "passive"))
      (node (ref "T66") (pin "7") (pinfunction "D1_7") (pintype "passive"))
    )
    (net (code "230") (name "/RLEDG33") (class "Default")
      (node (ref "T68") (pin "6") (pinfunction "D1_6") (pintype "passive"))
      (node (ref "T68") (pin "7") (pinfunction "D1_7") (pintype "passive"))
    )
    (net (code "231") (name "/RLEDG34") (class "Default")
      (node (ref "T70") (pin "6") (pinfunction "D1_6") (pintype "passive"))
      (node (ref "T70") (pin "7") (pinfunction "D1_7") (pintype "passive"))
    )
    (net (code "232") (name "/RLEDG35") (class "Default")
      (node (ref "T72") (pin "6") (pinfunction "D1_6") (pintype "passive"))
      (node (ref "T72") (pin "7") (pinfunction "D1_7") (pintype "passive"))
    )
    (net (code "233") (name "/RLEDG36") (class "Default")
      (node (ref "T74") (pin "6") (pinfunction "D1_6") (pintype "passive"))
      (node (ref "T74") (pin "7") (pinfunction "D1_7") (pintype "passive"))
    )
    (net (code "234") (name "/RLEDG37") (class "Default")
      (node (ref "T76") (pin "6") (pinfunction "D1_6") (pintype "passive"))
      (node (ref "T76") (pin "7") (pinfunction "D1_7") (pintype "passive"))
    )
    (net (code "235") (name "/RLEDG38") (class "Default")
      (node (ref "T78") (pin "6") (pinfunction "D1_6") (pintype "passive"))
      (node (ref "T78") (pin "7") (pinfunction "D1_7") (pintype "passive"))
    )
    (net (code "236") (name "/RLEDG39") (class "Default")
      (node (ref "T80") (pin "6") (pinfunction "D1_6") (pintype "passive"))
      (node (ref "T80") (pin "7") (pinfunction "D1_7") (pintype "passive"))
    )
    (net (code "237") (name "/RLEDG40") (class "Default")
      (node (ref "T82") (pin "6") (pinfunction "D1_6") (pintype "passive"))
      (node (ref "T82") (pin "7") (pinfunction "D1_7") (pintype "passive"))
    )
    (net (code "238") (name "/RLEDG41") (class "Default")
      (node (ref "T84") (pin "6") (pinfunction "D1_6") (pintype "passive"))
      (node (ref "T84") (pin "7") (pinfunction "D1_7") (pintype "passive"))
    )
    (net (code "239") (name "/RLEDG42") (class "Default")
      (node (ref "T86") (pin "6") (pinfunction "D1_6") (pintype "passive"))
      (node (ref "T86") (pin "7") (pinfunction "D1_7") (pintype "passive"))
    )
    (net (code "240") (name "/RLEDG43") (class "Default")
      (node (ref "T88") (pin "6") (pinfunction "D1_6") (pintype "passive"))
      (node (ref "T88") (pin "7") (pinfunction "D1_7") (pintype "passive"))
    )
    (net (code "241") (name "/RLEDG44") (class "Default")
      (node (ref "T90") (pin "6") (pinfunction "D1_6") (pintype "passive"))
      (node (ref "T90") (pin "7") (pinfunction "D1_7") (pintype "passive"))
    )
    (net (code "242") (name "/RLEDG45") (class "Default")
      (node (ref "T92") (pin "6") (pinfunction "D1_6") (pintype "passive"))
      (node (ref "T92") (pin "7") (pinfunction "D1_7") (pintype "passive"))
    )
    (net (code "243") (name "/RLEDG46") (class "Default")
      (node (ref "T94") (pin "6") (pinfunction "D1_6") (pintype "passive"))
      (node (ref "T94") (pin "7") (pinfunction "D1_7") (pintype "passive"))
    )
    (net (code "244") (name "/RLEDG47") (class "Default")
      (node (ref "T96") (pin "6") (pinfunction "D1_6") (pintype "passive"))
      (node (ref "T96") (pin "7") (pinfunction "D1_7") (pintype "passive"))
    )
    (net (code "246") (name "/RLEDR0") (class "Default")
      (node (ref "T1") (pin "6") (pinfunction "D1_6") (pintype "passive"))
      (node (ref "T1") (pin "7") (pinfunction "D1_7") (pintype "passive"))
    )
    (net (code "247") (name "/RLEDR1") (class "Default")
      (node (ref "T3") (pin "6") (pinfunction "D1_6") (pintype "passive"))
      (node (ref "T3") (pin "7") (pinfunction "D1_7") (pintype "passive"))
    )
    (net (code "248") (name "/RLEDR2") (class "Default")
      (node (ref "T5") (pin "6") (pinfunction "D1_6") (pintype "passive"))
      (node (ref "T5") (pin "7") (pinfunction "D1_7") (pintype "passive"))
    )
    (net (code "249") (name "/RLEDR3") (class "Default")
      (node (ref "T7") (pin "6") (pinfunction "D1_6") (pintype "passive"))
      (node (ref "T7") (pin "7") (pinfunction "D1_7") (pintype "passive"))
    )
    (net (code "250") (name "/RLEDR4") (class "Default")
      (node (ref "T9") (pin "6") (pinfunction "D1_6") (pintype "passive"))
      (node (ref "T9") (pin "7") (pinfunction "D1_7") (pintype "passive"))
    )
    (net (code "251") (name "/RLEDR5") (class "Default")
      (node (ref "T11") (pin "6") (pinfunction "D1_6") (pintype "passive"))
      (node (ref "T11") (pin "7") (pinfunction "D1_7") (pintype "passive"))
    )
    (net (code "252") (name "/RLEDR6") (class "Default")
      (node (ref "T13") (pin "6") (pinfunction "D1_6") (pintype "passive"))
      (node (ref "T13") (pin "7") (pinfunction "D1_7") (pintype "passive"))
    )
    (net (code "253") (name "/RLEDR7") (class "Default")
      (node (ref "T15") (pin "6") (pinfunction "D1_6") (pintype "passive"))
      (node (ref "T15") (pin "7") (pinfunction "D1_7") (pintype "passive"))
    )
    (net (code "254") (name "/RLEDR8") (class "Default")
      (node (ref "T17") (pin "6") (pinfunction "D1_6") (pintype "passive"))
      (node (ref "T17") (pin "7") (pinfunction "D1_7") (pintype "passive"))
    )
    (net (code "255") (name "/RLEDR9") (class "Default")
      (node (ref "T19") (pin "6") (pinfunction "D1_6") (pintype "passive"))
      (node (ref "T19") (pin "7") (pinfunction "D1_7") (pintype "passive"))
    )
    (net (code "256") (name "/RLEDR10") (class "Default")
      (node (ref "T21") (pin "6") (pinfunction "D1_6") (pintype "passive"))
      (node (ref "T21") (pin "7") (pinfunction "D1_7") (pintype "passive"))
    )
    (net (code "257") (name "/RLEDR11") (class "Default")
      (node (ref "T23") (pin "6") (pinfunction "D1_6") (pintype "passive"))
      (node (ref "T23") (pin "7") (pinfunction "D1_7") (pintype "passive"))
    )
    (net (code "258") (name "/RLEDR12") (class "Default")
      (node (ref "T25") (pin "6") (pinfunction "D1_6") (pintype "passive"))
      (node (ref "T25") (pin "7") (pinfunction "D1_7") (pintype "passive"))
    )
    (net (code "259") (name "/RLEDR13") (class "Default")
      (node (ref "T27") (pin "6") (pinfunction "D1_6") (pintype "passive"))
      (node (ref "T27") (pin "7") (pinfunction "D1_7") (pintype "passive"))
    )
    (net (code "260") (name "/RLEDR14") (class "Default")
      (node (ref "T29") (pin "6") (pinfunction "D1_6") (pintype "passive"))
      (node (ref "T29") (pin "7") (pinfunction "D1_7") (pintype "passive"))
    )
    (net (code "261") (name "/RLEDR15") (class "Default")
      (node (ref "T31") (pin "6") (pinfunction "D1_6") (pintype "passive"))
      (node (ref "T31") (pin "7") (pinfunction "D1_7") (pintype "passive"))
    )
    (net (code "262") (name "/RLEDR16") (class "Default")
      (node (ref "T33") (pin "6") (pinfunction "D1_6") (pintype "passive"))
      (node (ref "T33") (pin "7") (pinfunction "D1_7") (pintype "passive"))
    )
    (net (code "263") (name "/RLEDR17") (class "Default")
      (node (ref "T35") (pin "6") (pinfunction "D1_6") (pintype "passive"))
      (node (ref "T35") (pin "7") (pinfunction "D1_7") (pintype "passive"))
    )
    (net (code "264") (name "/RLEDR18") (class "Default")
      (node (ref "T37") (pin "6") (pinfunction "D1_6") (pintype "passive"))
      (node (ref "T37") (pin "7") (pinfunction "D1_7") (pintype "passive"))
    )
    (net (code "265") (name "/RLEDR19") (class "Default")
      (node (ref "T39") (pin "6") (pinfunction "D1_6") (pintype "passive"))
      (node (ref "T39") (pin "7") (pinfunction "D1_7") (pintype "passive"))
    )
    (net (code "266") (name "/RLEDR20") (class "Default")
      (node (ref "T41") (pin "6") (pinfunction "D1_6") (pintype "passive"))
      (node (ref "T41") (pin "7") (pinfunction "D1_7") (pintype "passive"))
    )
    (net (code "267") (name "/RLEDR21") (class "Default")
      (node (ref "T43") (pin "6") (pinfunction "D1_6") (pintype "passive"))
      (node (ref "T43") (pin "7") (pinfunction "D1_7") (pintype "passive"))
    )
    (net (code "268") (name "/RLEDR22") (class "Default")
      (node (ref "T45") (pin "6") (pinfunction "D1_6") (pintype "passive"))
      (node (ref "T45") (pin "7") (pinfunction "D1_7") (pintype "passive"))
    )
    (net (code "269") (name "/RLEDR23") (class "Default")
      (node (ref "T47") (pin "6") (pinfunction "D1_6") (pintype "passive"))
      (node (ref "T47") (pin "7") (pinfunction "D1_7") (pintype "passive"))
    )
    (net (code "270") (name "/RLEDR24") (class "Default")
      (node (ref "T49") (pin "6") (pinfunction "D1_6") (pintype "passive"))
      (node (ref "T49") (pin "7") (pinfunction "D1_7") (pintype "passive"))
    )
    (net (code "271") (name "/RLEDR25") (class "Default")
      (node (ref "T51") (pin "6") (pinfunction "D1_6") (pintype "passive"))
      (node (ref "T51") (pin "7") (pinfunction "D1_7") (pintype "passive"))
    )
    (net (code "272") (name "/RLEDR26") (class "Default")
      (node (ref "T53") (pin "6") (pinfunction "D1_6") (pintype "passive"))
      (node (ref "T53") (pin "7") (pinfunction "D1_7") (pintype "passive"))
    )
    (net (code "273") (name "/RLEDR27") (class "Default")
      (node (ref "T55") (pin "6") (pinfunction "D1_6") (pintype "passive"))
      (node (ref "T55") (pin "7") (pinfunction "D1_7") (pintype "passive"))
    )
    (net (code "274") (name "/RLEDR28") (class "Default")
      (node (ref "T57") (pin "6") (pinfunction "D1_6") (pintype "passive"))
      (node (ref "T57") (pin "7") (pinfunction "D1_7") (pintype "passive"))
    )
    (net (code "275") (name "/RLEDR29") (class "Default")
      (node (ref "T59") (pin "6") (pinfunction "D1_6") (pintype "passive"))
      (node (ref "T59") (pin "7") (pinfunction "D1_7") (pintype "passive"))
    )
    (net (code "276") (name "/RLEDR30") (class "Default")
      (node (ref "T61") (pin "6") (pinfunction "D1_6") (pintype "passive"))
      (node (ref "T61") (pin "7") (pinfunction "D1_7") (pintype "passive"))
    )
    (net (code "277") (name "/RLEDR31") (class "Default")
      (node (ref "T63") (pin "6") (pinfunction "D1_6") (pintype "passive"))
      (node (ref "T63") (pin "7") (pinfunction "D1_7") (pintype "passive"))
    )
    (net (code "278") (name "/RLEDR32") (class "Default")
      (node (ref "T65") (pin "6") (pinfunction "D1_6") (pintype "passive"))
      (node (ref "T65") (pin "7") (pinfunction "D1_7") (pintype "passive"))
    )
    (net (code "279") (name "/RLEDR33") (class "Default")
      (node (ref "T67") (pin "6") (pinfunction "D1_6") (pintype "passive"))
      (node (ref "T67") (pin "7") (pinfunction "D1_7") (pintype "passive"))
    )
    (net (code "280") (name "/RLEDR34") (class "Default")
      (node (ref "T69") (pin "6") (pinfunction "D1_6") (pintype "passive"))
      (node (ref "T69") (pin "7") (pinfunction "D1_7") (pintype "passive"))
    )
    (net (code "281") (name "/RLEDR35") (class "Default")
      (node (ref "T71") (pin "6") (pinfunction "D1_6") (pintype "passive"))
      (node (ref "T71") (pin "7") (pinfunction "D1_7") (pintype "passive"))
    )
    (net (code "282") (name "/RLEDR36") (class "Default")
      (node (ref "T73") (pin "6") (pinfunction "D1_6") (pintype "passive"))
      (node (ref "T73") (pin "7") (pinfunction "D1_7") (pintype "passive"))
    )
    (net (code "283") (name "/RLEDR37") (class "Default")
      (node (ref "T75") (pin "6") (pinfunction "D1_6") (pintype "passive"))
      (node (ref "T75") (pin "7") (pinfunction "D1_7") (pintype "passive"))
    )
    (net (code "284") (name "/RLEDR38") (class "Default")
      (node (ref "T77") (pin "6") (pinfunction "D1_6") (pintype "passive"))
      (node (ref "T77") (pin "7") (pinfunction "D1_7") (pintype "passive"))
    )
    (net (code "285") (name "/RLEDR39") (class "Default")
      (node (ref "T79") (pin "6") (pinfunction "D1_6") (pintype "passive"))
      (node (ref "T79") (pin "7") (pinfunction "D1_7") (pintype "passive"))
    )
    (net (code "286") (name "/RLEDR40") (class "Default")
      (node (ref "T81") (pin "6") (pinfunction "D1_6") (pintype "passive"))
      (node (ref "T81") (pin "7") (pinfunction "D1_7") (pintype "passive"))
    )
    (net (code "287") (name "/RLEDR41") (class "Default")
      (node (ref "T83") (pin "6") (pinfunction "D1_6") (pintype "passive"))
      (node (ref "T83") (pin "7") (pinfunction "D1_7") (pintype "passive"))
    )
    (net (code "288") (name "/RLEDR42") (class "Default")
      (node (ref "T85") (pin "6") (pinfunction "D1_6") (pintype "passive"))
      (node (ref "T85") (pin "7") (pinfunction "D1_7") (pintype "passive"))
    )
    (net (code "289") (name "/RLEDR43") (class "Default")
      (node (ref "T87") (pin "6") (pinfunction "D1_6") (pintype "passive"))
      (node (ref "T87") (pin "7") (pinfunction "D1_7") (pintype "passive"))
    )
    (net (code "290") (name "/RLEDR44") (class "Default")
      (node (ref "T89") (pin "6") (pinfunction "D1_6") (pintype "passive"))
      (node (ref "T89") (pin "7") (pinfunction "D1_7") (pintype "passive"))
    )
    (net (code "291") (name "/RLEDR45") (class "Default")
      (node (ref "T91") (pin "6") (pinfunction "D1_6") (pintype "passive"))
      (node (ref "T91") (pin "7") (pinfunction "D1_7") (pintype "passive"))
    )
    (net (code "292") (name "/RLEDR46") (class "Default")
      (node (ref "T93") (pin "6") (pinfunction "D1_6") (pintype "passive"))
      (node (ref "T93") (pin "7") (pinfunction "D1_7") (pintype "passive"))
    )
    (net (code "293") (name "/RLEDR47") (class "Default")
      (node (ref "T95") (pin "6") (pinfunction "D1_6") (pintype "passive"))
      (node (ref "T95") (pin "7") (pinfunction "D1_7") (pintype "passive"))
    )
    (net (code "295") (name "GND") (class "Default")
      (node (ref "T1") (pin "1") (pinfunction "S1_1") (pintype "passive"))
      (node (ref "T1") (pin "4") (pinfunction "S2_4") (pintype "passive"))
      (node (ref "T10") (pin "1") (pinfunction "S1_1") (pintype "passive"))
      (node (ref "T10") (pin "4") (pinfunction "S2_4") (pintype "passive"))
      (node (ref "T11") (pin "1") (pinfunction "S1_1") (pintype "passive"))
      (node (ref "T11") (pin "4") (pinfunction "S2_4") (pintype "passive"))
      (node (ref "T12") (pin "1") (pinfunction "S1_1") (pintype "passive"))
      (node (ref "T12") (pin "4") (pinfunction "S2_4") (pintype "passive"))
      (node (ref "T13") (pin "1") (pinfunction "S1_1") (pintype "passive"))
      (node (ref "T13") (pin "4") (pinfunction "S2_4") (pintype "passive"))
      (node (ref "T14") (pin "1") (pinfunction "S1_1") (pintype "passive"))
      (node (ref "T14") (pin "4") (pinfunction "S2_4") (pintype "passive"))
      (node (ref "T15") (pin "1") (pinfunction "S1_1") (pintype "passive"))
      (node (ref "T15") (pin "4") (pinfunction "S2_4") (pintype "passive"))
      (node (ref "T16") (pin "1") (pinfunction "S1_1") (pintype "passive"))
      (node (ref "T16") (pin "4") (pinfunction "S2_4") (pintype "passive"))
      (node (ref "T17") (pin "1") (pinfunction "S1_1") (pintype "passive"))
      (node (ref "T17") (pin "4") (pinfunction "S2_4") (pintype "passive"))
      (node (ref "T18") (pin "1") (pinfunction "S1_1") (pintype "passive"))
      (node (ref "T18") (pin "4") (pinfunction "S2_4") (pintype "passive"))
      (node (ref "T19") (pin "1") (pinfunction "S1_1") (pintype "passive"))
      (node (ref "T19") (pin "4") (pinfunction "S2_4") (pintype "passive"))
      (node (ref "T2") (pin "1") (pinfunction "S1_1") (pintype "passive"))
      (node (ref "T2") (pin "4") (pinfunction "S2_4") (pintype "passive"))
      (node (ref "T20") (pin "1") (pinfunction "S1_1") (pintype "passive"))
      (node (ref "T20") (pin "4") (pinfunction "S2_4") (pintype "passive"))
      (node (ref "T21") (pin "1") (pinfunction "S1_1") (pintype "passive"))
      (node (ref "T21") (pin "4") (pinfunction "S2_4") (pintype "passive"))
      (node (ref "T22") (pin "1") (pinfunction "S1_1") (pintype "passive"))
      (node (ref "T22") (pin "4") (pinfunction "S2_4") (pintype "passive"))
      (node (ref "T23") (pin "1") (pinfunction "S1_1") (pintype "passive"))
      (node (ref "T23") (pin "4") (pinfunction "S2_4") (pintype "passive"))
      (node (ref "T24") (pin "1") (pinfunction "S1_1") (pintype "passive"))
      (node (ref "T24") (pin "4") (pinfunction "S2_4") (pintype "passive"))
      (node (ref "T25") (pin "1") (pinfunction "S1_1") (pintype "passive"))
      (node (ref "T25") (pin "4") (pinfunction "S2_4") (pintype "passive"))
      (node (ref "T26") (pin "1") (pinfunction "S1_1") (pintype "passive"))
      (node (ref "T26") (pin "4") (pinfunction "S2_4") (pintype "passive"))
      (node (ref "T27") (pin "1") (pinfunction "S1_1") (pintype "passive"))
      (node (ref "T27") (pin "4") (pinfunction "S2_4") (pintype "passive"))
      (node (ref "T28") (pin "1") (pinfunction "S1_1") (pintype "passive"))
      (node (ref "T28") (pin "4") (pinfunction "S2_4") (pintype "passive"))
      (node (ref "T29") (pin "1") (pinfunction "S1_1") (pintype "passive"))
      (node (ref "T29") (pin "4") (pinfunction "S2_4") (pintype "passive"))
      (node (ref "T3") (pin "1") (pinfunction "S1_1") (pintype "passive"))
      (node (ref "T3") (pin "4") (pinfunction "S2_4") (pintype "passive"))
      (node (ref "T30") (pin "1") (pinfunction "S1_1") (pintype "passive"))
      (node (ref "T30") (pin "4") (pinfunction "S2_4") (pintype "passive"))
      (node (ref "T31") (pin "1") (pinfunction "S1_1") (pintype "passive"))
      (node (ref "T31") (pin "4") (pinfunction "S2_4") (pintype "passive"))
      (node (ref "T32") (pin "1") (pinfunction "S1_1") (pintype "passive"))
      (node (ref "T32") (pin "4") (pinfunction "S2_4") (pintype "passive"))
      (node (ref "T33") (pin "1") (pinfunction "S1_1") (pintype "passive"))
      (node (ref "T33") (pin "4") (pinfunction "S2_4") (pintype "passive"))
      (node (ref "T34") (pin "1") (pinfunction "S1_1") (pintype "passive"))
      (node (ref "T34") (pin "4") (pinfunction "S2_4") (pintype "passive"))
      (node (ref "T35") (pin "1") (pinfunction "S1_1") (pintype "passive"))
      (node (ref "T35") (pin "4") (pinfunction "S2_4") (pintype "passive"))
      (node (ref "T36") (pin "1") (pinfunction "S1_1") (pintype "passive"))
      (node (ref "T36") (pin "4") (pinfunction "S2_4") (pintype "passive"))
      (node (ref "T37") (pin "1") (pinfunction "S1_1") (pintype "passive"))
      (node (ref "T37") (pin "4") (pinfunction "S2_4") (pintype "passive"))
      (node (ref "T38") (pin "1") (pinfunction "S1_1") (pintype "passive"))
      (node (ref "T38") (pin "4") (pinfunction "S2_4") (pintype "passive"))
      (node (ref "T39") (pin "1") (pinfunction "S1_1") (pintype "passive"))
      (node (ref "T39") (pin "4") (pinfunction "S2_4") (pintype "passive"))
      (node (ref "T4") (pin "1") (pinfunction "S1_1") (pintype "passive"))
      (node (ref "T4") (pin "4") (pinfunction "S2_4") (pintype "passive"))
      (node (ref "T40") (pin "1") (pinfunction "S1_1") (pintype "passive"))
      (node (ref "T40") (pin "4") (pinfunction "S2_4") (pintype "passive"))
      (node (ref "T41") (pin "1") (pinfunction "S1_1") (pintype "passive"))
      (node (ref "T41") (pin "4") (pinfunction "S2_4") (pintype "passive"))
      (node (ref "T42") (pin "1") (pinfunction "S1_1") (pintype "passive"))
      (node (ref "T42") (pin "4") (pinfunction "S2_4") (pintype "passive"))
      (node (ref "T43") (pin "1") (pinfunction "S1_1") (pintype "passive"))
      (node (ref "T43") (pin "4") (pinfunction "S2_4") (pintype "passive"))
      (node (ref "T44") (pin "1") (pinfunction "S1_1") (pintype "passive"))
      (node (ref "T44") (pin "4") (pinfunction "S2_4") (pintype "passive"))
      (node (ref "T45") (pin "1") (pinfunction "S1_1") (pintype "passive"))
      (node (ref "T45") (pin "4") (pinfunction "S2_4") (pintype "passive"))
      (node (ref "T46") (pin "1") (pinfunction "S1_1") (pintype "passive"))
      (node (ref "T46") (pin "4") (pinfunction "S2_4") (pintype "passive"))
      (node (ref "T47") (pin "1") (pinfunction "S1_1") (pintype "passive"))
      (node (ref "T47") (pin "4") (pinfunction "S2_4") (pintype "passive"))
      (node (ref "T48") (pin "1") (pinfunction "S1_1") (pintype "passive"))
      (node (ref "T48") (pin "4") (pinfunction "S2_4") (pintype "passive"))
      (node (ref "T49") (pin "1") (pinfunction "S1_1") (pintype "passive"))
      (node (ref "T49") (pin "4") (pinfunction "S2_4") (pintype "passive"))
      (node (ref "T5") (pin "1") (pinfunction "S1_1") (pintype "passive"))
      (node (ref "T5") (pin "4") (pinfunction "S2_4") (pintype "passive"))
      (node (ref "T50") (pin "1") (pinfunction "S1_1") (pintype "passive"))
      (node (ref "T50") (pin "4") (pinfunction "S2_4") (pintype "passive"))
      (node (ref "T51") (pin "1") (pinfunction "S1_1") (pintype "passive"))
      (node (ref "T51") (pin "4") (pinfunction "S2_4") (pintype "passive"))
      (node (ref "T52") (pin "1") (pinfunction "S1_1") (pintype "passive"))
      (node (ref "T52") (pin "4") (pinfunction "S2_4") (pintype "passive"))
      (node (ref "T53") (pin "1") (pinfunction "S1_1") (pintype "passive"))
      (node (ref "T53") (pin "4") (pinfunction "S2_4") (pintype "passive"))
      (node (ref "T54") (pin "1") (pinfunction "S1_1") (pintype "passive"))
      (node (ref "T54") (pin "4") (pinfunction "S2_4") (pintype "passive"))
      (node (ref "T55") (pin "1") (pinfunction "S1_1") (pintype "passive"))
      (node (ref "T55") (pin "4") (pinfunction "S2_4") (pintype "passive"))
      (node (ref "T56") (pin "1") (pinfunction "S1_1") (pintype "passive"))
      (node (ref "T56") (pin "4") (pinfunction "S2_4") (pintype "passive"))
      (node (ref "T57") (pin "1") (pinfunction "S1_1") (pintype "passive"))
      (node (ref "T57") (pin "4") (pinfunction "S2_4") (pintype "passive"))
      (node (ref "T58") (pin "1") (pinfunction "S1_1") (pintype "passive"))
      (node (ref "T58") (pin "4") (pinfunction "S2_4") (pintype "passive"))
      (node (ref "T59") (pin "1") (pinfunction "S1_1") (pintype "passive"))
      (node (ref "T59") (pin "4") (pinfunction "S2_4") (pintype "passive"))
      (node (ref "T6") (pin "1") (pinfunction "S1_1") (pintype "passive"))
      (node (ref "T6") (pin "4") (pinfunction "S2_4") (pintype "passive"))
      (node (ref "T60") (pin "1") (pinfunction "S1_1") (pintype "passive"))
      (node (ref "T60") (pin "4") (pinfunction "S2_4") (pintype "passive"))
      (node (ref "T61") (pin "1") (pinfunction "S1_1") (pintype "passive"))
      (node (ref "T61") (pin "4") (pinfunction "S2_4") (pintype "passive"))
      (node (ref "T62") (pin "1") (pinfunction "S1_1") (pintype "passive"))
      (node (ref "T62") (pin "4") (pinfunction "S2_4") (pintype "passive"))
      (node (ref "T63") (pin "1") (pinfunction "S1_1") (pintype "passive"))
      (node (ref "T63") (pin "4") (pinfunction "S2_4") (pintype "passive"))
      (node (ref "T64") (pin "1") (pinfunction "S1_1") (pintype "passive"))
      (node (ref "T64") (pin "4") (pinfunction "S2_4") (pintype "passive"))
      (node (ref "T65") (pin "1") (pinfunction "S1_1") (pintype "passive"))
      (node (ref "T65") (pin "4") (pinfunction "S2_4") (pintype "passive"))
      (node (ref "T66") (pin "1") (pinfunction "S1_1") (pintype "passive"))
      (node (ref "T66") (pin "4") (pinfunction "S2_4") (pintype "passive"))
      (node (ref "T67") (pin "1") (pinfunction "S1_1") (pintype "passive"))
      (node (ref "T67") (pin "4") (pinfunction "S2_4") (pintype "passive"))
      (node (ref "T68") (pin "1") (pinfunction "S1_1") (pintype "passive"))
      (node (ref "T68") (pin "4") (pinfunction "S2_4") (pintype "passive"))
      (node (ref "T69") (pin "1") (pinfunction "S1_1") (pintype "passive"))
      (node (ref "T69") (pin "4") (pinfunction "S2_4") (pintype "passive"))
      (node (ref "T7") (pin "1") (pinfunction "S1_1") (pintype "passive"))
      (node (ref "T7") (pin "4") (pinfunction "S2_4") (pintype "passive"))
      (node (ref "T70") (pin "1") (pinfunction "S1_1") (pintype "passive"))
      (node (ref "T70") (pin "4") (pinfunction "S2_4") (pintype "passive"))
      (node (ref "T71") (pin "1") (pinfunction "S1_1") (pintype "passive"))
      (node (ref "T71") (pin "4") (pinfunction "S2_4") (pintype "passive"))
      (node (ref "T72") (pin "1") (pinfunction "S1_1") (pintype "passive"))
      (node (ref "T72") (pin "4") (pinfunction "S2_4") (pintype "passive"))
      (node (ref "T73") (pin "1") (pinfunction "S1_1") (pintype "passive"))
      (node (ref "T73") (pin "4") (pinfunction "S2_4") (pintype "passive"))
      (node (ref "T74") (pin "1") (pinfunction "S1_1") (pintype "passive"))
      (node (ref "T74") (pin "4") (pinfunction "S2_4") (pintype "passive"))
      (node (ref "T75") (pin "1") (pinfunction "S1_1") (pintype "passive"))
      (node (ref "T75") (pin "4") (pinfunction "S2_4") (pintype "passive"))
      (node (ref "T76") (pin "1") (pinfunction "S1_1") (pintype "passive"))
      (node (ref "T76") (pin "4") (pinfunction "S2_4") (pintype "passive"))
      (node (ref "T77") (pin "1") (pinfunction "S1_1") (pintype "passive"))
      (node (ref "T77") (pin "4") (pinfunction "S2_4") (pintype "passive"))
      (node (ref "T78") (pin "1") (pinfunction "S1_1") (pintype "passive"))
      (node (ref "T78") (pin "4") (pinfunction "S2_4") (pintype "passive"))
      (node (ref "T79") (pin "1") (pinfunction "S1_1") (pintype "passive"))
      (node (ref "T79") (pin "4") (pinfunction "S2_4") (pintype "passive"))
      (node (ref "T8") (pin "1") (pinfunction "S1_1") (pintype "passive"))
      (node (ref "T8") (pin "4") (pinfunction "S2_4") (pintype "passive"))
      (node (ref "T80") (pin "1") (pinfunction "S1_1") (pintype "passive"))
      (node (ref "T80") (pin "4") (pinfunction "S2_4") (pintype "passive"))
      (node (ref "T81") (pin "1") (pinfunction "S1_1") (pintype "passive"))
      (node (ref "T81") (pin "4") (pinfunction "S2_4") (pintype "passive"))
      (node (ref "T82") (pin "1") (pinfunction "S1_1") (pintype "passive"))
      (node (ref "T82") (pin "4") (pinfunction "S2_4") (pintype "passive"))
      (node (ref "T83") (pin "1") (pinfunction "S1_1") (pintype "passive"))
      (node (ref "T83") (pin "4") (pinfunction "S2_4") (pintype "passive"))
      (node (ref "T84") (pin "1") (pinfunction "S1_1") (pintype "passive"))
      (node (ref "T84") (pin "4") (pinfunction "S2_4") (pintype "passive"))
      (node (ref "T85") (pin "1") (pinfunction "S1_1") (pintype "passive"))
      (node (ref "T85") (pin "4") (pinfunction "S2_4") (pintype "passive"))
      (node (ref "T86") (pin "1") (pinfunction "S1_1") (pintype "passive"))
      (node (ref "T86") (pin "4") (pinfunction "S2_4") (pintype "passive"))
      (node (ref "T87") (pin "1") (pinfunction "S1_1") (pintype "passive"))
      (node (ref "T87") (pin "4") (pinfunction "S2_4") (pintype "passive"))
      (node (ref "T88") (pin "1") (pinfunction "S1_1") (pintype "passive"))
      (node (ref "T88") (pin "4") (pinfunction "S2_4") (pintype "passive"))
      (node (ref "T89") (pin "1") (pinfunction "S1_1") (pintype "passive"))
      (node (ref "T89") (pin "4") (pinfunction "S2_4") (pintype "passive"))
      (node (ref "T9") (pin "1") (pinfunction "S1_1") (pintype "passive"))
      (node (ref "T9") (pin "4") (pinfunction "S2_4") (pintype "passive"))
      (node (ref "T90") (pin "1") (pinfunction "S1_1") (pintype "passive"))
      (node (ref "T90") (pin "4") (pinfunction "S2_4") (pintype "passive"))
      (node (ref "T91") (pin "1") (pinfunction "S1_1") (pintype "passive"))
      (node (ref "T91") (pin "4") (pinfunction "S2_4") (pintype "passive"))
      (node (ref "T92") (pin "1") (pinfunction "S1_1") (pintype "passive"))
      (node (ref "T92") (pin "4") (pinfunction "S2_4") (pintype "passive"))
      (node (ref "T93") (pin "1") (pinfunction "S1_1") (pintype "passive"))
      (node (ref "T93") (pin "4") (pinfunction "S2_4") (pintype "passive"))
      (node (ref "T94") (pin "1") (pinfunction "S1_1") (pintype "passive"))
      (node (ref "T94") (pin "4") (pinfunction "S2_4") (pintype "passive"))
      (node (ref "T95") (pin "1") (pinfunction "S1_1") (pintype "passive"))
      (node (ref "T95") (pin "4") (pinfunction "S2_4") (pintype "passive"))
      (node (ref "T96") (pin "1") (pinfunction "S1_1") (pintype "passive"))
      (node (ref "T96") (pin "4") (pinfunction "S2_4") (pintype "passive"))
    )
    (net (code "296") (name "Net-(T2B-D2-Pad3)") (class "Default")
      (node (ref "T2") (pin "3") (pinfunction "D2_3") (pintype "passive"))
      (node (ref "T2") (pin "8") (pinfunction "D2_8") (pintype "passive"))
    )
    (net (code "297") (name "Net-(T4B-D2-Pad3)") (class "Default")
      (node (ref "T4") (pin "3") (pinfunction "D2_3") (pintype "passive"))
      (node (ref "T4") (pin "8") (pinfunction "D2_8") (pintype "passive"))
    )
    (net (code "298") (name "Net-(T6B-D2-Pad3)") (class "Default")
      (node (ref "T6") (pin "3") (pinfunction "D2_3") (pintype "passive"))
      (node (ref "T6") (pin "8") (pinfunction "D2_8") (pintype "passive"))
    )
    (net (code "299") (name "Net-(T8B-D2-Pad3)") (class "Default")
      (node (ref "T8") (pin "3") (pinfunction "D2_3") (pintype "passive"))
      (node (ref "T8") (pin "8") (pinfunction "D2_8") (pintype "passive"))
    )
    (net (code "300") (name "Net-(T10B-D2-Pad3)") (class "Default")
      (node (ref "T10") (pin "3") (pinfunction "D2_3") (pintype "passive"))
      (node (ref "T10") (pin "8") (pinfunction "D2_8") (pintype "passive"))
    )
    (net (code "301") (name "Net-(T12B-D2-Pad3)") (class "Default")
      (node (ref "T12") (pin "3") (pinfunction "D2_3") (pintype "passive"))
      (node (ref "T12") (pin "8") (pinfunction "D2_8") (pintype "passive"))
    )
    (net (code "302") (name "Net-(T14B-D2-Pad3)") (class "Default")
      (node (ref "T14") (pin "3") (pinfunction "D2_3") (pintype "passive"))
      (node (ref "T14") (pin "8") (pinfunction "D2_8") (pintype "passive"))
    )
    (net (code "303") (name "Net-(T16B-D2-Pad3)") (class "Default")
      (node (ref "T16") (pin "3") (pinfunction "D2_3") (pintype "passive"))
      (node (ref "T16") (pin "8") (pinfunction "D2_8") (pintype "passive"))
    )
    (net (code "304") (name "Net-(T18B-D2-Pad3)") (class "Default")
      (node (ref "T18") (pin "3") (pinfunction "D2_3") (pintype "passive"))
      (node (ref "T18") (pin "8") (pinfunction "D2_8") (pintype "passive"))
    )
    (net (code "305") (name "Net-(T20B-D2-Pad3)") (class "Default")
      (node (ref "T20") (pin "3") (pinfunction "D2_3") (pintype "passive"))
      (node (ref "T20") (pin "8") (pinfunction "D2_8") (pintype "passive"))
    )
    (net (code "306") (name "Net-(T22B-D2-Pad3)") (class "Default")
      (node (ref "T22") (pin "3") (pinfunction "D2_3") (pintype "passive"))
      (node (ref "T22") (pin "8") (pinfunction "D2_8") (pintype "passive"))
    )
    (net (code "307") (name "Net-(T24B-D2-Pad3)") (class "Default")
      (node (ref "T24") (pin "3") (pinfunction "D2_3") (pintype "passive"))
      (node (ref "T24") (pin "8") (pinfunction "D2_8") (pintype "passive"))
    )
    (net (code "308") (name "Net-(T26B-D2-Pad3)") (class "Default")
      (node (ref "T26") (pin "3") (pinfunction "D2_3") (pintype "passive"))
      (node (ref "T26") (pin "8") (pinfunction "D2_8") (pintype "passive"))
    )
    (net (code "309") (name "Net-(T28B-D2-Pad3)") (class "Default")
      (node (ref "T28") (pin "3") (pinfunction "D2_3") (pintype "passive"))
      (node (ref "T28") (pin "8") (pinfunction "D2_8") (pintype "passive"))
    )
    (net (code "310") (name "Net-(T30B-D2-Pad3)") (class "Default")
      (node (ref "T30") (pin "3") (pinfunction "D2_3") (pintype "passive"))
      (node (ref "T30") (pin "8") (pinfunction "D2_8") (pintype "passive"))
    )
    (net (code "311") (name "Net-(T32B-D2-Pad3)") (class "Default")
      (node (ref "T32") (pin "3") (pinfunction "D2_3") (pintype "passive"))
      (node (ref "T32") (pin "8") (pinfunction "D2_8") (pintype "passive"))
    )
    (net (code "312") (name "Net-(T34B-D2-Pad3)") (class "Default")
      (node (ref "T34") (pin "3") (pinfunction "D2_3") (pintype "passive"))
      (node (ref "T34") (pin "8") (pinfunction "D2_8") (pintype "passive"))
    )
    (net (code "313") (name "Net-(T36B-D2-Pad3)") (class "Default")
      (node (ref "T36") (pin "3") (pinfunction "D2_3") (pintype "passive"))
      (node (ref "T36") (pin "8") (pinfunction "D2_8") (pintype "passive"))
    )
    (net (code "314") (name "Net-(T38B-D2-Pad3)") (class "Default")
      (node (ref "T38") (pin "3") (pinfunction "D2_3") (pintype "passive"))
      (node (ref "T38") (pin "8") (pinfunction "D2_8") (pintype "passive"))
    )
    (net (code "315") (name "Net-(T40B-D2-Pad3)") (class "Default")
      (node (ref "T40") (pin "3") (pinfunction "D2_3") (pintype "passive"))
      (node (ref "T40") (pin "8") (pinfunction "D2_8") (pintype "passive"))
    )
    (net (code "316") (name "Net-(T42B-D2-Pad3)") (class "Default")
      (node (ref "T42") (pin "3") (pinfunction "D2_3") (pintype "passive"))
      (node (ref "T42") (pin "8") (pinfunction "D2_8") (pintype "passive"))
    )
    (net (code "317") (name "Net-(T44B-D2-Pad3)") (class "Default")
      (node (ref "T44") (pin "3") (pinfunction "D2_3") (pintype "passive"))
      (node (ref "T44") (pin "8") (pinfunction "D2_8") (pintype "passive"))
    )
    (net (code "318") (name "Net-(T46B-D2-Pad3)") (class "Default")
      (node (ref "T46") (pin "3") (pinfunction "D2_3") (pintype "passive"))
      (node (ref "T46") (pin "8") (pinfunction "D2_8") (pintype "passive"))
    )
    (net (code "319") (name "Net-(T48B-D2-Pad3)") (class "Default")
      (node (ref "T48") (pin "3") (pinfunction "D2_3") (pintype "passive"))
      (node (ref "T48") (pin "8") (pinfunction "D2_8") (pintype "passive"))
    )
    (net (code "320") (name "Net-(T50B-D2-Pad3)") (class "Default")
      (node (ref "T50") (pin "3") (pinfunction "D2_3") (pintype "passive"))
      (node (ref "T50") (pin "8") (pinfunction "D2_8") (pintype "passive"))
    )
    (net (code "321") (name "Net-(T52B-D2-Pad3)") (class "Default")
      (node (ref "T52") (pin "3") (pinfunction "D2_3") (pintype "passive"))
      (node (ref "T52") (pin "8") (pinfunction "D2_8") (pintype "passive"))
    )
    (net (code "322") (name "Net-(T54B-D2-Pad3)") (class "Default")
      (node (ref "T54") (pin "3") (pinfunction "D2_3") (pintype "passive"))
      (node (ref "T54") (pin "8") (pinfunction "D2_8") (pintype "passive"))
    )
    (net (code "323") (name "Net-(T56B-D2-Pad3)") (class "Default")
      (node (ref "T56") (pin "3") (pinfunction "D2_3") (pintype "passive"))
      (node (ref "T56") (pin "8") (pinfunction "D2_8") (pintype "passive"))
    )
    (net (code "324") (name "Net-(T58B-D2-Pad3)") (class "Default")
      (node (ref "T58") (pin "3") (pinfunction "D2_3") (pintype "passive"))
      (node (ref "T58") (pin "8") (pinfunction "D2_8") (pintype "passive"))
    )
    (net (code "325") (name "Net-(T60B-D2-Pad3)") (class "Default")
      (node (ref "T60") (pin "3") (pinfunction "D2_3") (pintype "passive"))
      (node (ref "T60") (pin "8") (pinfunction "D2_8") (pintype "passive"))
    )
    (net (code "326") (name "Net-(T62B-D2-Pad3)") (class "Default")
      (node (ref "T62") (pin "3") (pinfunction "D2_3") (pintype "passive"))
      (node (ref "T62") (pin "8") (pinfunction "D2_8") (pintype "passive"))
    )
    (net (code "327") (name "Net-(T64B-D2-Pad3)") (class "Default")
      (node (ref "T64") (pin "3") (pinfunction "D2_3") (pintype "passive"))
      (node (ref "T64") (pin "8") (pinfunction "D2_8") (pintype "passive"))
    )
    (net (code "328") (name "Net-(T66B-D2-Pad3)") (class "Default")
      (node (ref "T66") (pin "3") (pinfunction "D2_3") (pintype "passive"))
      (node (ref "T66") (pin "8") (pinfunction "D2_8") (pintype "passive"))
    )
    (net (code "329") (name "Net-(T68B-D2-Pad3)") (class "Default")
      (node (ref "T68") (pin "3") (pinfunction "D2_3") (pintype "passive"))
      (node (ref "T68") (pin "8") (pinfunction "D2_8") (pintype "passive"))
    )
    (net (code "330") (name "Net-(T70B-D2-Pad3)") (class "Default")
      (node (ref "T70") (pin "3") (pinfunction "D2_3") (pintype "passive"))
      (node (ref "T70") (pin "8") (pinfunction "D2_8") (pintype "passive"))
    )
    (net (code "331") (name "Net-(T72B-D2-Pad3)") (class "Default")
      (node (ref "T72") (pin "3") (pinfunction "D2_3") (pintype "passive"))
      (node (ref "T72") (pin "8") (pinfunction "D2_8") (pintype "passive"))
    )
    (net (code "332") (name "Net-(T74B-D2-Pad3)") (class "Default")
      (node (ref "T74") (pin "3") (pinfunction "D2_3") (pintype "passive"))
      (node (ref "T74") (pin "8") (pinfunction "D2_8") (pintype "passive"))
    )
    (net (code "333") (name "Net-(T76B-D2-Pad3)") (class "Default")
      (node (ref "T76") (pin "3") (pinfunction "D2_3") (pintype "passive"))
      (node (ref "T76") (pin "8") (pinfunction "D2_8") (pintype "passive"))
    )
    (net (code "334") (name "Net-(T78B-D2-Pad3)") (class "Default")
      (node (ref "T78") (pin "3") (pinfunction "D2_3") (pintype "passive"))
      (node (ref "T78") (pin "8") (pinfunction "D2_8") (pintype "passive"))
    )
    (net (code "335") (name "Net-(T80B-D2-Pad3)") (class "Default")
      (node (ref "T80") (pin "3") (pinfunction "D2_3") (pintype "passive"))
      (node (ref "T80") (pin "8") (pinfunction "D2_8") (pintype "passive"))
    )
    (net (code "336") (name "Net-(T82B-D2-Pad3)") (class "Default")
      (node (ref "T82") (pin "3") (pinfunction "D2_3") (pintype "passive"))
      (node (ref "T82") (pin "8") (pinfunction "D2_8") (pintype "passive"))
    )
    (net (code "337") (name "Net-(T84B-D2-Pad3)") (class "Default")
      (node (ref "T84") (pin "3") (pinfunction "D2_3") (pintype "passive"))
      (node (ref "T84") (pin "8") (pinfunction "D2_8") (pintype "passive"))
    )
    (net (code "338") (name "Net-(T86B-D2-Pad3)") (class "Default")
      (node (ref "T86") (pin "3") (pinfunction "D2_3") (pintype "passive"))
      (node (ref "T86") (pin "8") (pinfunction "D2_8") (pintype "passive"))
    )
    (net (code "339") (name "Net-(T88B-D2-Pad3)") (class "Default")
      (node (ref "T88") (pin "3") (pinfunction "D2_3") (pintype "passive"))
      (node (ref "T88") (pin "8") (pinfunction "D2_8") (pintype "passive"))
    )
    (net (code "340") (name "Net-(T90B-D2-Pad3)") (class "Default")
      (node (ref "T90") (pin "3") (pinfunction "D2_3") (pintype "passive"))
      (node (ref "T90") (pin "8") (pinfunction "D2_8") (pintype "passive"))
    )
    (net (code "341") (name "Net-(T92B-D2-Pad3)") (class "Default")
      (node (ref "T92") (pin "3") (pinfunction "D2_3") (pintype "passive"))
      (node (ref "T92") (pin "8") (pinfunction "D2_8") (pintype "passive"))
    )
    (net (code "342") (name "Net-(T94B-D2-Pad3)") (class "Default")
      (node (ref "T94") (pin "3") (pinfunction "D2_3") (pintype "passive"))
      (node (ref "T94") (pin "8") (pinfunction "D2_8") (pintype "passive"))
    )
    (net (code "343") (name "Net-(T96B-D2-Pad3)") (class "Default")
      (node (ref "T96") (pin "3") (pinfunction "D2_3") (pintype "passive"))
      (node (ref "T96") (pin "8") (pinfunction "D2_8") (pintype "passive"))
    )
    (net (code "344") (name "unconnected-(T2B-G2-Pad5)") (class "Default")
      (node (ref "T2") (pin "5") (pinfunction "G2_5") (pintype "passive"))
    )
    (net (code "345") (name "unconnected-(T4B-G2-Pad5)") (class "Default")
      (node (ref "T4") (pin "5") (pinfunction "G2_5") (pintype "passive"))
    )
    (net (code "346") (name "unconnected-(T6B-G2-Pad5)") (class "Default")
      (node (ref "T6") (pin "5") (pinfunction "G2_5") (pintype "passive"))
    )
    (net (code "347") (name "unconnected-(T8B-G2-Pad5)") (class "Default")
      (node (ref "T8") (pin "5") (pinfunction "G2_5") (pintype "passive"))
    )
    (net (code "348") (name "unconnected-(T10B-G2-Pad5)") (class "Default")
      (node (ref "T10") (pin "5") (pinfunction "G2_5") (pintype "passive"))
    )
    (net (code "349") (name "unconnected-(T12B-G2-Pad5)") (class "Default")
      (node (ref "T12") (pin "5") (pinfunction "G2_5") (pintype "passive"))
    )
    (net (code "350") (name "unconnected-(T14B-G2-Pad5)") (class "Default")
      (node (ref "T14") (pin "5") (pinfunction "G2_5") (pintype "passive"))
    )
    (net (code "351") (name "unconnected-(T16B-G2-Pad5)") (class "Default")
      (node (ref "T16") (pin "5") (pinfunction "G2_5") (pintype "passive"))
    )
    (net (code "352") (name "unconnected-(T18B-G2-Pad5)") (class "Default")
      (node (ref "T18") (pin "5") (pinfunction "G2_5") (pintype "passive"))
    )
    (net (code "353") (name "unconnected-(T20B-G2-Pad5)") (class "Default")
      (node (ref "T20") (pin "5") (pinfunction "G2_5") (pintype "passive"))
    )
    (net (code "354") (name "unconnected-(T22B-G2-Pad5)") (class "Default")
      (node (ref "T22") (pin "5") (pinfunction "G2_5") (pintype "passive"))
    )
    (net (code "355") (name "unconnected-(T24B-G2-Pad5)") (class "Default")
      (node (ref "T24") (pin "5") (pinfunction "G2_5") (pintype "passive"))
    )
    (net (code "356") (name "unconnected-(T26B-G2-Pad5)") (class "Default")
      (node (ref "T26") (pin "5") (pinfunction "G2_5") (pintype "passive"))
    )
    (net (code "357") (name "unconnected-(T28B-G2-Pad5)") (class "Default")
      (node (ref "T28") (pin "5") (pinfunction "G2_5") (pintype "passive"))
    )
    (net (code "358") (name "unconnected-(T30B-G2-Pad5)") (class "Default")
      (node (ref "T30") (pin "5") (pinfunction "G2_5") (pintype "passive"))
    )
    (net (code "359") (name "unconnected-(T32B-G2-Pad5)") (class "Default")
      (node (ref "T32") (pin "5") (pinfunction "G2_5") (pintype "passive"))
    )
    (net (code "360") (name "unconnected-(T34B-G2-Pad5)") (class "Default")
      (node (ref "T34") (pin "5") (pinfunction "G2_5") (pintype "passive"))
    )
    (net (code "361") (name "unconnected-(T36B-G2-Pad5)") (class "Default")
      (node (ref "T36") (pin "5") (pinfunction "G2_5") (pintype "passive"))
    )
    (net (code "362") (name "unconnected-(T38B-G2-Pad5)") (class "Default")
      (node (ref "T38") (pin "5") (pinfunction "G2_5") (pintype "passive"))
    )
    (net (code "363") (name "unconnected-(T40B-G2-Pad5)") (class "Default")
      (node (ref "T40") (pin "5") (pinfunction "G2_5") (pintype "passive"))
    )
    (net (code "364") (name "unconnected-(T42B-G2-Pad5)") (class "Default")
      (node (ref "T42") (pin "5") (pinfunction "G2_5") (pintype "passive"))
    )
    (net (code "365") (name "unconnected-(T44B-G2-Pad5)") (class "Default")
      (node (ref "T44") (pin "5") (pinfunction "G2_5") (pintype "passive"))
    )
    (net (code "366") (name "unconnected-(T46B-G2-Pad5)") (class "Default")
      (node (ref "T46") (pin "5") (pinfunction "G2_5") (pintype "passive"))
    )
    (net (code "367") (name "unconnected-(T48B-G2-Pad5)") (class "Default")
      (node (ref "T48") (pin "5") (pinfunction "G2_5") (pintype "passive"))
    )
    (net (code "368") (name "unconnected-(T50B-G2-Pad5)") (class "Default")
      (node (ref "T50") (pin "5") (pinfunction "G2_5") (pintype "passive"))
    )
    (net (code "369") (name "unconnected-(T52B-G2-Pad5)") (class "Default")
      (node (ref "T52") (pin "5") (pinfunction "G2_5") (pintype "passive"))
    )
    (net (code "370") (name "unconnected-(T54B-G2-Pad5)") (class "Default")
      (node (ref "T54") (pin "5") (pinfunction "G2_5") (pintype "passive"))
    )
    (net (code "371") (name "unconnected-(T56B-G2-Pad5)") (class "Default")
      (node (ref "T56") (pin "5") (pinfunction "G2_5") (pintype "passive"))
    )
    (net (code "372") (name "unconnected-(T58B-G2-Pad5)") (class "Default")
      (node (ref "T58") (pin "5") (pinfunction "G2_5") (pintype "passive"))
    )
    (net (code "373") (name "unconnected-(T60B-G2-Pad5)") (class "Default")
      (node (ref "T60") (pin "5") (pinfunction "G2_5") (pintype "passive"))
    )
    (net (code "374") (name "unconnected-(T62B-G2-Pad5)") (class "Default")
      (node (ref "T62") (pin "5") (pinfunction "G2_5") (pintype "passive"))
    )
    (net (code "375") (name "unconnected-(T64B-G2-Pad5)") (class "Default")
      (node (ref "T64") (pin "5") (pinfunction "G2_5") (pintype "passive"))
    )
    (net (code "376") (name "unconnected-(T66B-G2-Pad5)") (class "Default")
      (node (ref "T66") (pin "5") (pinfunction "G2_5") (pintype "passive"))
    )
    (net (code "377") (name "unconnected-(T68B-G2-Pad5)") (class "Default")
      (node (ref "T68") (pin "5") (pinfunction "G2_5") (pintype "passive"))
    )
    (net (code "378") (name "unconnected-(T70B-G2-Pad5)") (class "Default")
      (node (ref "T70") (pin "5") (pinfunction "G2_5") (pintype "passive"))
    )
    (net (code "379") (name "unconnected-(T72B-G2-Pad5)") (class "Default")
      (node (ref "T72") (pin "5") (pinfunction "G2_5") (pintype "passive"))
    )
    (net (code "380") (name "unconnected-(T74B-G2-Pad5)") (class "Default")
      (node (ref "T74") (pin "5") (pinfunction "G2_5") (pintype "passive"))
    )
    (net (code "381") (name "unconnected-(T76B-G2-Pad5)") (class "Default")
      (node (ref "T76") (pin "5") (pinfunction "G2_5") (pintype "passive"))
    )
    (net (code "382") (name "unconnected-(T78B-G2-Pad5)") (class "Default")
      (node (ref "T78") (pin "5") (pinfunction "G2_5") (pintype "passive"))
    )
    (net (code "383") (name "unconnected-(T80B-G2-Pad5)") (class "Default")
      (node (ref "T80") (pin "5") (pinfunction "G2_5") (pintype "passive"))
    )
    (net (code "384") (name "unconnected-(T82B-G2-Pad5)") (class "Default")
      (node (ref "T82") (pin "5") (pinfunction "G2_5") (pintype "passive"))
    )
    (net (code "385") (name "unconnected-(T84B-G2-Pad5)") (class "Default")
      (node (ref "T84") (pin "5") (pinfunction "G2_5") (pintype "passive"))
    )
    (net (code "386") (name "unconnected-(T86B-G2-Pad5)") (class "Default")
      (node (ref "T86") (pin "5") (pinfunction "G2_5") (pintype "passive"))
    )
    (net (code "387") (name "unconnected-(T88B-G2-Pad5)") (class "Default")
      (node (ref "T88") (pin "5") (pinfunction "G2_5") (pintype "passive"))
    )
    (net (code "388") (name "unconnected-(T90B-G2-Pad5)") (class "Default")
      (node (ref "T90") (pin "5") (pinfunction "G2_5") (pintype "passive"))
    )
    (net (code "389") (name "unconnected-(T92B-G2-Pad5)") (class "Default")
      (node (ref "T92") (pin "5") (pinfunction "G2_5") (pintype "passive"))
    )
    (net (code "390") (name "unconnected-(T94B-G2-Pad5)") (class "Default")
      (node (ref "T94") (pin "5") (pinfunction "G2_5") (pintype "passive"))
    )
    (net (code "391") (name "unconnected-(T96B-G2-Pad5)") (class "Default")
      (node (ref "T96") (pin "5") (pinfunction "G2_5") (pintype "passive"))
    )
  )
)
